# A-14732-40023-REPRODUCTION.net
KiCad netlist of a schematic drawn in EAGLE
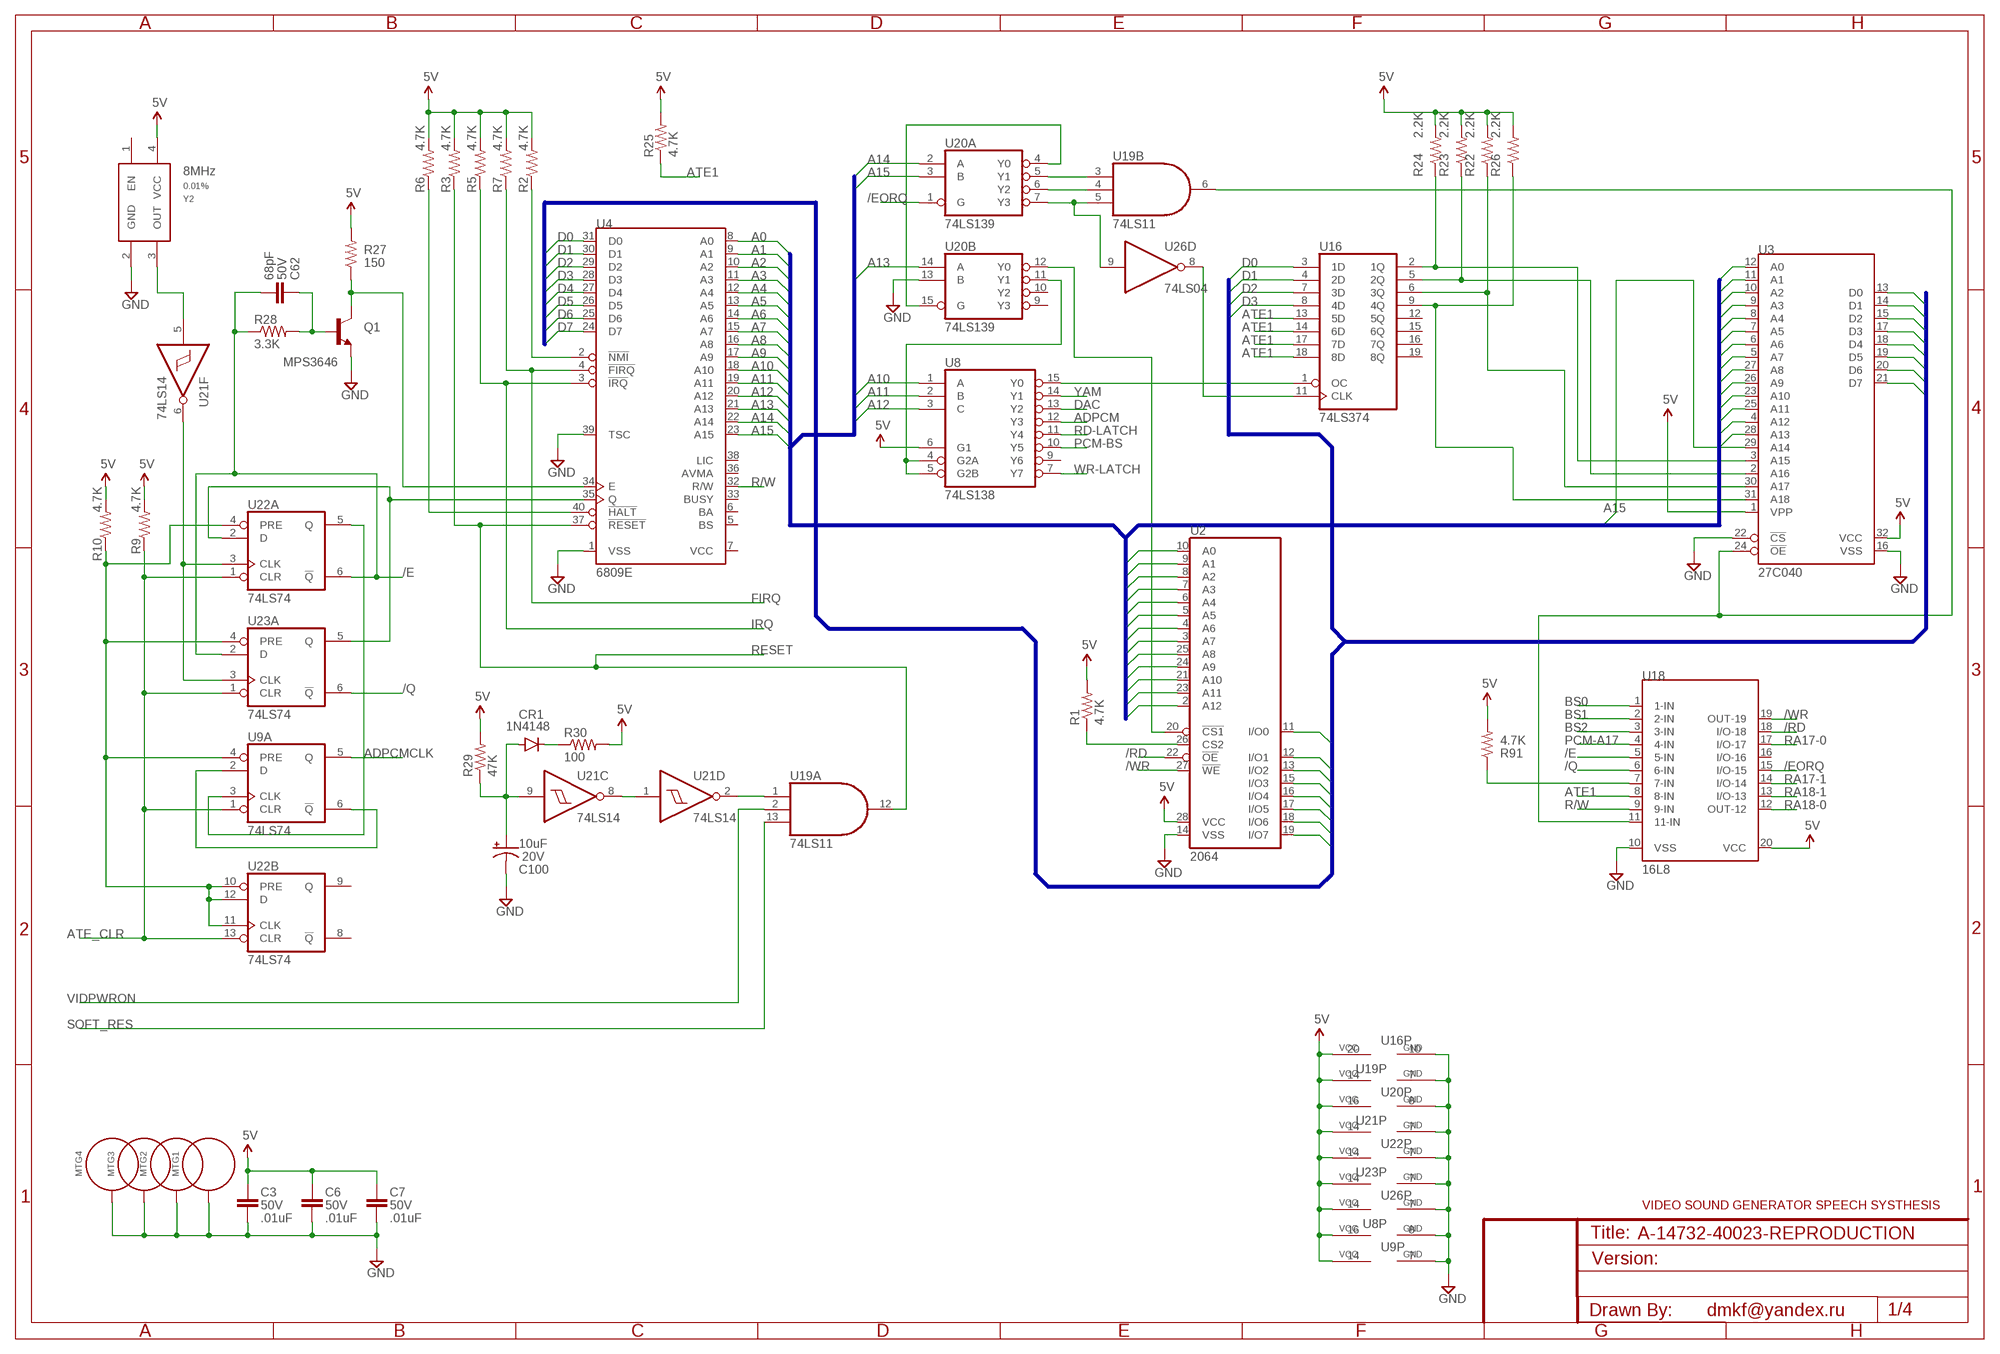
[diagram p0: schematic, sheet 1]
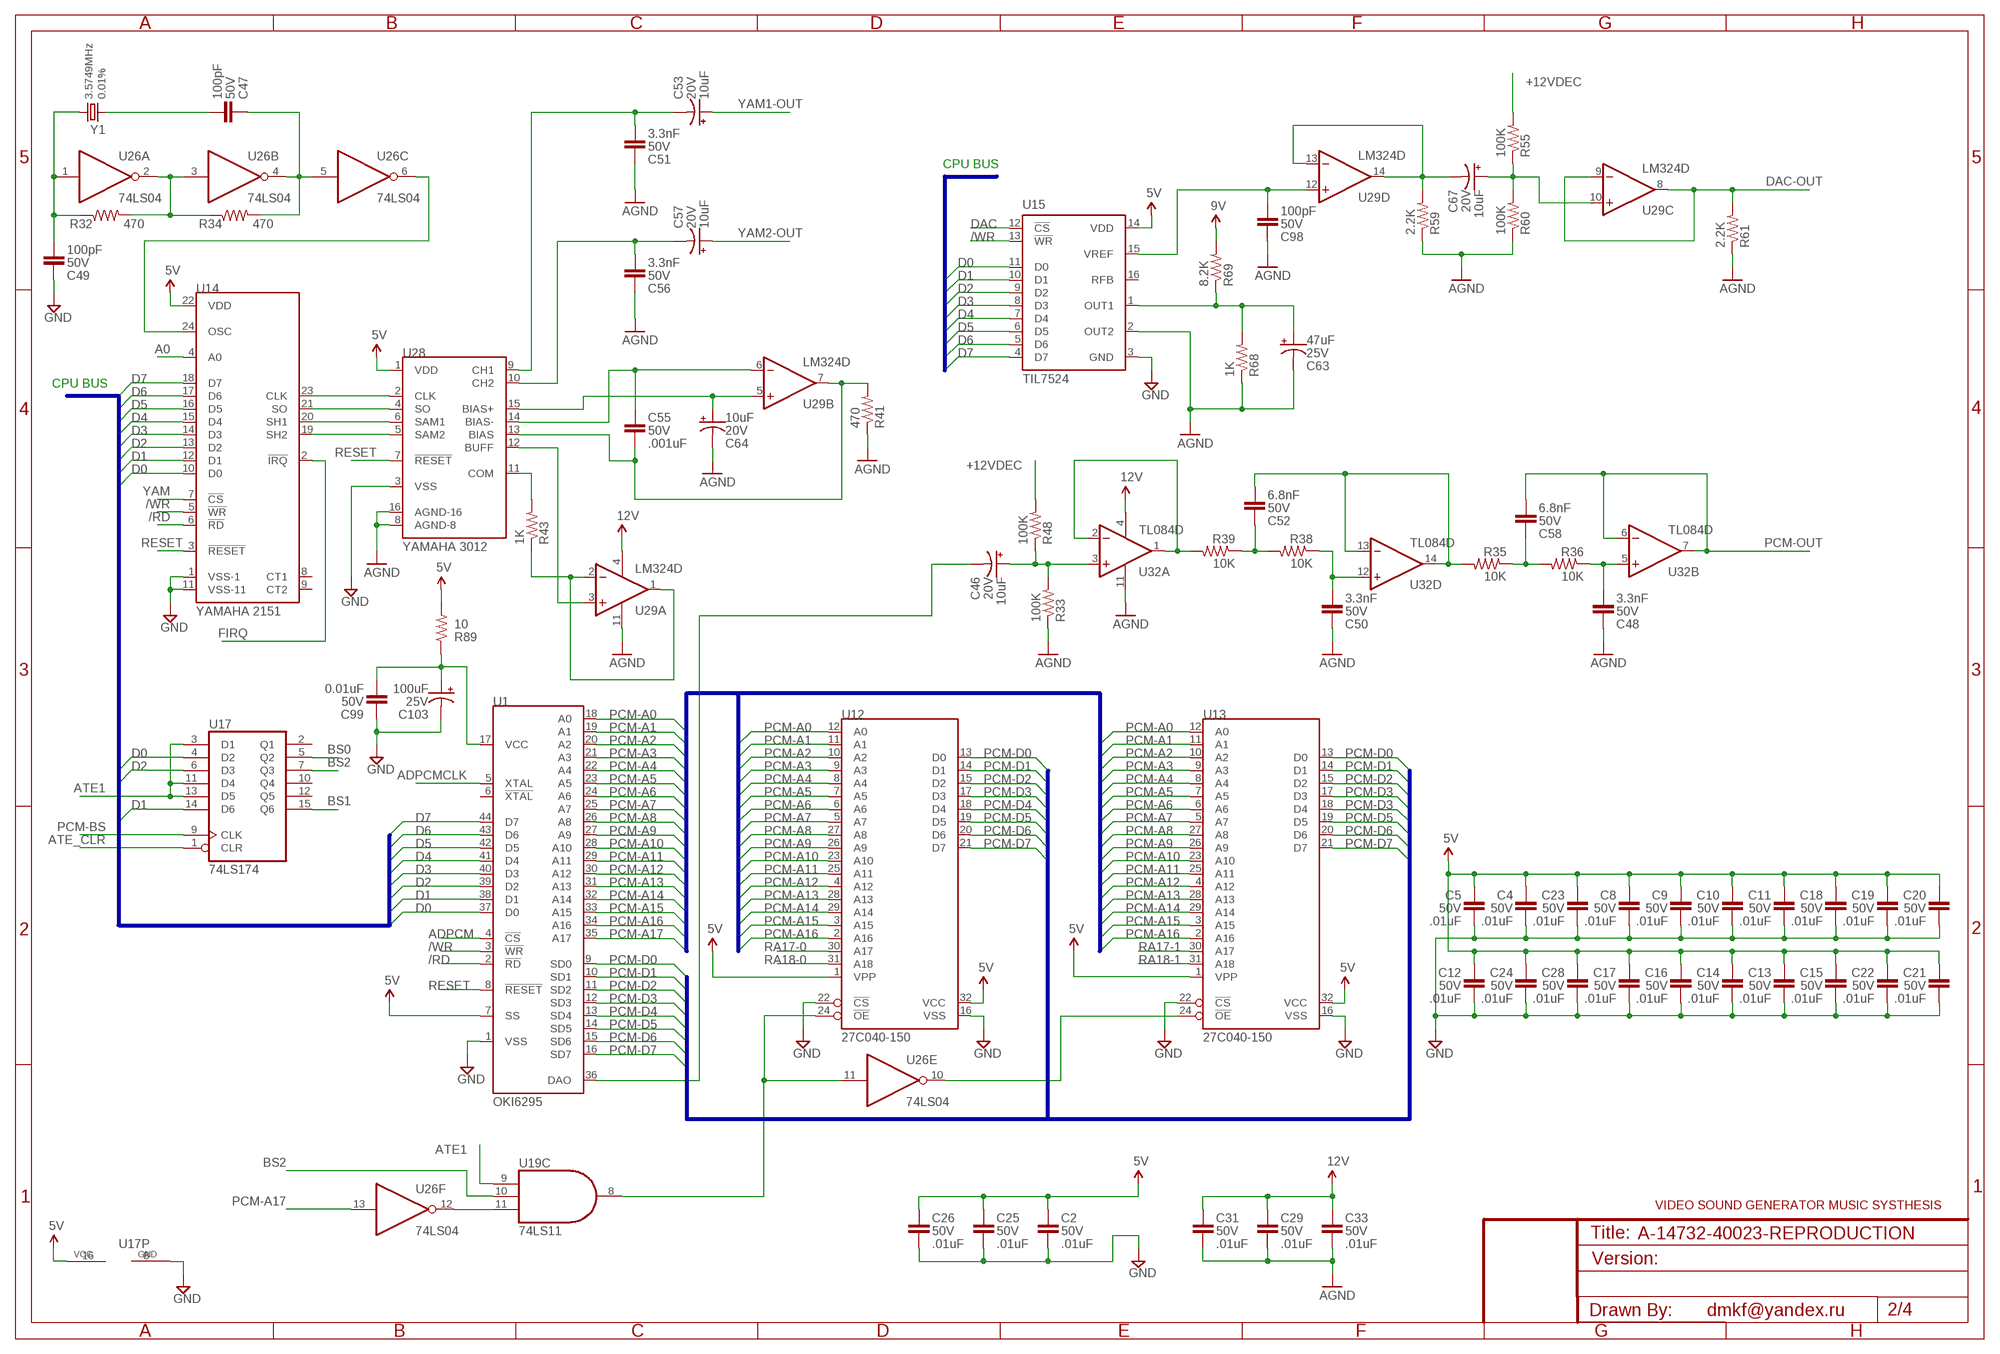
[diagram p1: schematic, sheet 2]
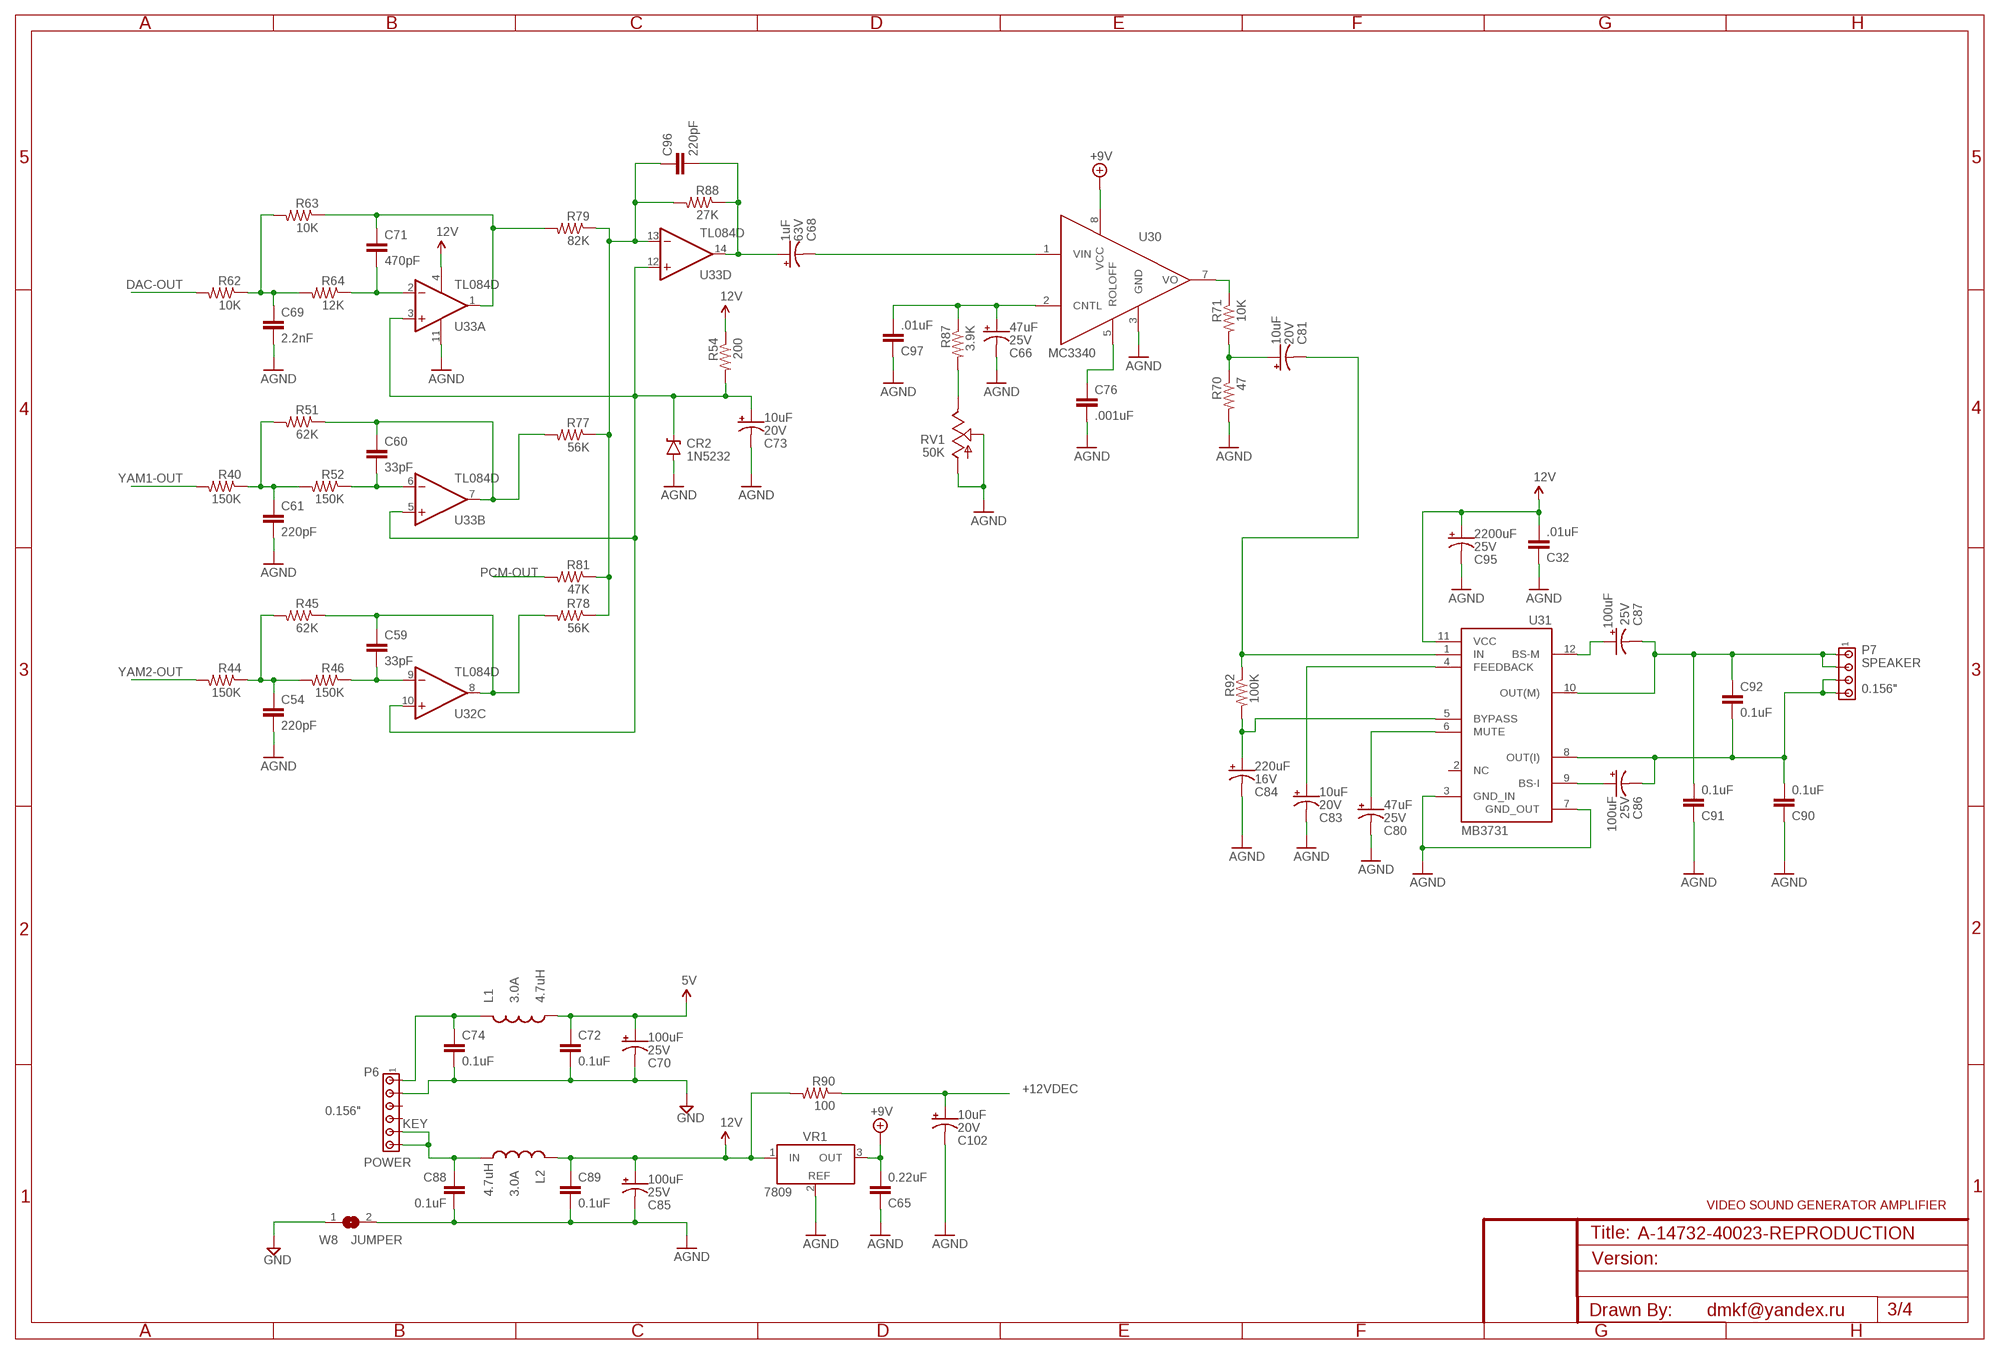
[diagram p2: schematic, sheet 3]
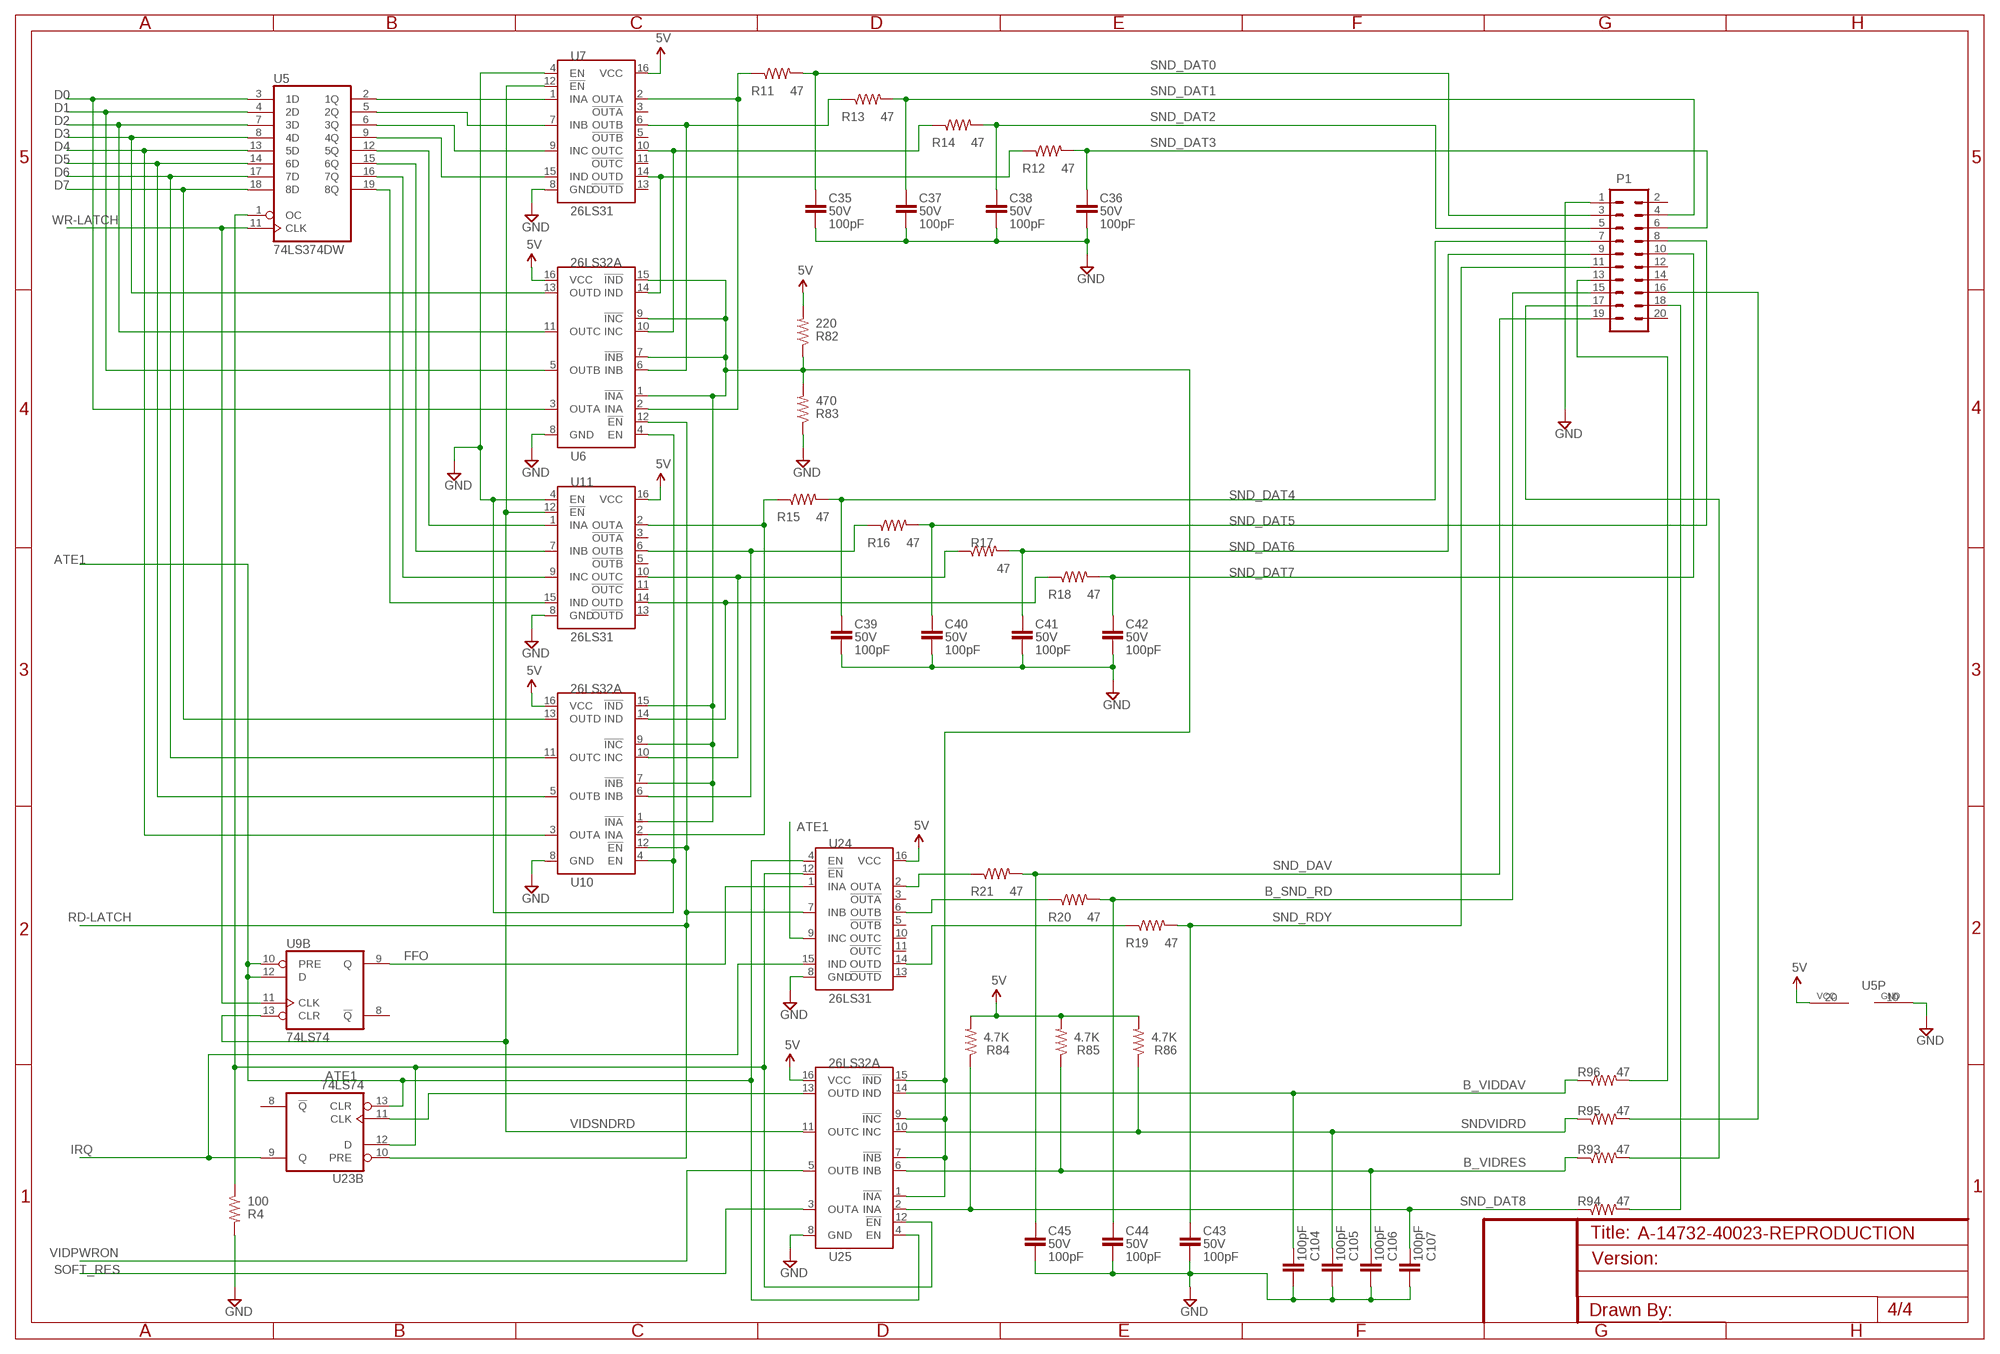
[diagram p3: schematic, sheet 4]

(export (version "E")
  (design (tool "Eeschema 10.0.6"))
  (components
    (comp (ref "C35")
      (value "100pF")
      (footprint "eagle-import:0805")
      (fields (field (name "VOLTAGE") "50V"))
      (libsource (lib "eagle-import") (part "CAP0805"))
    )
    (comp (ref "C36")
      (value "100pF")
      (footprint "eagle-import:0805")
      (fields (field (name "VOLTAGE") "50V"))
      (libsource (lib "eagle-import") (part "CAP0805"))
    )
    (comp (ref "C37")
      (value "100pF")
      (footprint "eagle-import:0805")
      (fields (field (name "VOLTAGE") "50V"))
      (libsource (lib "eagle-import") (part "CAP0805"))
    )
    (comp (ref "C38")
      (value "100pF")
      (footprint "eagle-import:0805")
      (fields (field (name "VOLTAGE") "50V"))
      (libsource (lib "eagle-import") (part "CAP0805"))
    )
    (comp (ref "C39")
      (value "100pF")
      (footprint "eagle-import:0805")
      (fields (field (name "VOLTAGE") "50V"))
      (libsource (lib "eagle-import") (part "CAP0805"))
    )
    (comp (ref "C40")
      (value "100pF")
      (footprint "eagle-import:0805")
      (fields (field (name "VOLTAGE") "50V"))
      (libsource (lib "eagle-import") (part "CAP0805"))
    )
    (comp (ref "C41")
      (value "100pF")
      (footprint "eagle-import:0805")
      (fields (field (name "VOLTAGE") "50V"))
      (libsource (lib "eagle-import") (part "CAP0805"))
    )
    (comp (ref "C42")
      (value "100pF")
      (footprint "eagle-import:0805")
      (fields (field (name "VOLTAGE") "50V"))
      (libsource (lib "eagle-import") (part "CAP0805"))
    )
    (comp (ref "C43")
      (value "100pF")
      (footprint "eagle-import:0805")
      (fields (field (name "VOLTAGE") "50V"))
      (libsource (lib "eagle-import") (part "CAP0805"))
    )
    (comp (ref "C44")
      (value "100pF")
      (footprint "eagle-import:0805")
      (fields (field (name "VOLTAGE") "50V"))
      (libsource (lib "eagle-import") (part "CAP0805"))
    )
    (comp (ref "C45")
      (value "100pF")
      (footprint "eagle-import:0805")
      (fields (field (name "VOLTAGE") "50V"))
      (libsource (lib "eagle-import") (part "CAP0805"))
    )
    (comp (ref "C104")
      (value "100pF")
      (footprint "eagle-import:0805")
      (fields (field (name "VOLTAGE") "50V"))
      (libsource (lib "eagle-import") (part "CAP0805"))
    )
    (comp (ref "C105")
      (value "100pF")
      (footprint "eagle-import:0805")
      (fields (field (name "VOLTAGE") "50V"))
      (libsource (lib "eagle-import") (part "CAP0805"))
    )
    (comp (ref "C106")
      (value "100pF")
      (footprint "eagle-import:0805")
      (fields (field (name "VOLTAGE") "50V"))
      (libsource (lib "eagle-import") (part "CAP0805"))
    )
    (comp (ref "C107")
      (value "100pF")
      (footprint "eagle-import:0805")
      (fields (field (name "VOLTAGE") "50V"))
      (libsource (lib "eagle-import") (part "CAP0805"))
    )
    (comp (ref "P1")
      (value "M10X2ROUND_NOSILK")
      (footprint "eagle-import:2X10_ROUND_NOSILK")
      (libsource (lib "eagle-import") (part "M10X2ROUND_NOSILK"))
    )
    (comp (ref "R4")
      (value "100")
      (footprint "eagle-import:0805")
      (libsource (lib "eagle-import") (part "RESISTOR0805-RES"))
    )
    (comp (ref "R11")
      (value "47")
      (footprint "eagle-import:0805")
      (libsource (lib "eagle-import") (part "RESISTOR0805-RES"))
    )
    (comp (ref "R12")
      (value "47")
      (footprint "eagle-import:0805")
      (libsource (lib "eagle-import") (part "RESISTOR0805-RES"))
    )
    (comp (ref "R13")
      (value "47")
      (footprint "eagle-import:0805")
      (libsource (lib "eagle-import") (part "RESISTOR0805-RES"))
    )
    (comp (ref "R14")
      (value "47")
      (footprint "eagle-import:0805")
      (libsource (lib "eagle-import") (part "RESISTOR0805-RES"))
    )
    (comp (ref "R15")
      (value "47")
      (footprint "eagle-import:R1206")
      (libsource (lib "eagle-import") (part "R-US_R1206"))
    )
    (comp (ref "R16")
      (value "47")
      (footprint "eagle-import:R1206")
      (libsource (lib "eagle-import") (part "R-US_R1206"))
    )
    (comp (ref "R17")
      (value "47")
      (footprint "eagle-import:R1206")
      (libsource (lib "eagle-import") (part "R-US_R1206"))
    )
    (comp (ref "R18")
      (value "47")
      (footprint "eagle-import:R1206")
      (libsource (lib "eagle-import") (part "R-US_R1206"))
    )
    (comp (ref "R19")
      (value "47")
      (footprint "eagle-import:0805")
      (libsource (lib "eagle-import") (part "RESISTOR0805-RES"))
    )
    (comp (ref "R20")
      (value "47")
      (footprint "eagle-import:0805")
      (libsource (lib "eagle-import") (part "RESISTOR0805-RES"))
    )
    (comp (ref "R21")
      (value "47")
      (footprint "eagle-import:0805")
      (libsource (lib "eagle-import") (part "RESISTOR0805-RES"))
    )
    (comp (ref "R82")
      (value "220")
      (footprint "eagle-import:R1206")
      (libsource (lib "eagle-import") (part "R-US_R1206"))
    )
    (comp (ref "R83")
      (value "470")
      (footprint "eagle-import:R1206")
      (libsource (lib "eagle-import") (part "R-US_R1206"))
    )
    (comp (ref "R84")
      (value "4.7K")
      (footprint "eagle-import:0805")
      (libsource (lib "eagle-import") (part "RESISTOR0805-RES"))
    )
    (comp (ref "R85")
      (value "4.7K")
      (footprint "eagle-import:0805")
      (libsource (lib "eagle-import") (part "RESISTOR0805-RES"))
    )
    (comp (ref "R86")
      (value "4.7K")
      (footprint "eagle-import:0805")
      (libsource (lib "eagle-import") (part "RESISTOR0805-RES"))
    )
    (comp (ref "R93")
      (value "47")
      (footprint "eagle-import:0805")
      (libsource (lib "eagle-import") (part "RESISTOR0805-RES"))
    )
    (comp (ref "R94")
      (value "47")
      (footprint "eagle-import:0805")
      (libsource (lib "eagle-import") (part "RESISTOR0805-RES"))
    )
    (comp (ref "R95")
      (value "47")
      (footprint "eagle-import:0805")
      (libsource (lib "eagle-import") (part "RESISTOR0805-RES"))
    )
    (comp (ref "R96")
      (value "47")
      (footprint "eagle-import:0805")
      (libsource (lib "eagle-import") (part "RESISTOR0805-RES"))
    )
    (comp (ref "U5")
      (value "74LS374DW")
      (footprint "eagle-import:SO20W")
      (libsource (lib "eagle-import") (part "74374DWLS"))
    )
    (comp (ref "U6")
      (value "26LS32A")
      (footprint "eagle-import:SO16")
      (libsource (lib "eagle-import") (part "26LS32A"))
    )
    (comp (ref "U7")
      (value "26LS31")
      (footprint "eagle-import:SO16")
      (libsource (lib "eagle-import") (part "26LS31"))
    )
    (comp (ref "U9")
      (value "74LS74")
      (footprint "eagle-import:SO14")
      (libsource (lib "eagle-import") (part "7474DLS"))
    )
    (comp (ref "U10")
      (value "26LS32A")
      (footprint "eagle-import:SO16")
      (libsource (lib "eagle-import") (part "26LS32A"))
    )
    (comp (ref "U11")
      (value "26LS31")
      (footprint "eagle-import:SO16")
      (libsource (lib "eagle-import") (part "26LS31"))
    )
    (comp (ref "U23")
      (value "74LS74")
      (footprint "eagle-import:SO14")
      (libsource (lib "eagle-import") (part "7474DLS"))
    )
    (comp (ref "U24")
      (value "26LS31")
      (footprint "eagle-import:SO16")
      (libsource (lib "eagle-import") (part "26LS31"))
    )
    (comp (ref "U25")
      (value "26LS32A")
      (footprint "eagle-import:SO16")
      (libsource (lib "eagle-import") (part "26LS32A"))
    )
    (comp (ref "C2")
      (value ".01uF")
      (footprint "eagle-import:0805")
      (fields (field (name "VOLTAGE") "50V"))
      (libsource (lib "eagle-import") (part "CAP0805"))
    )
    (comp (ref "C4")
      (value ".01uF")
      (footprint "eagle-import:0805")
      (fields (field (name "VOLTAGE") "50V"))
      (libsource (lib "eagle-import") (part "CAP0805"))
    )
    (comp (ref "C5")
      (value ".01uF")
      (footprint "eagle-import:0805")
      (fields (field (name "VOLTAGE") "50V"))
      (libsource (lib "eagle-import") (part "CAP0805"))
    )
    (comp (ref "C8")
      (value ".01uF")
      (footprint "eagle-import:0805")
      (fields (field (name "VOLTAGE") "50V"))
      (libsource (lib "eagle-import") (part "CAP0805"))
    )
    (comp (ref "C9")
      (value ".01uF")
      (footprint "eagle-import:0805")
      (fields (field (name "VOLTAGE") "50V"))
      (libsource (lib "eagle-import") (part "CAP0805"))
    )
    (comp (ref "C10")
      (value ".01uF")
      (footprint "eagle-import:0805")
      (fields (field (name "VOLTAGE") "50V"))
      (libsource (lib "eagle-import") (part "CAP0805"))
    )
    (comp (ref "C11")
      (value ".01uF")
      (footprint "eagle-import:0805")
      (fields (field (name "VOLTAGE") "50V"))
      (libsource (lib "eagle-import") (part "CAP0805"))
    )
    (comp (ref "C12")
      (value ".01uF")
      (footprint "eagle-import:0805")
      (fields (field (name "VOLTAGE") "50V"))
      (libsource (lib "eagle-import") (part "CAP0805"))
    )
    (comp (ref "C13")
      (value ".01uF")
      (footprint "eagle-import:0805")
      (fields (field (name "VOLTAGE") "50V"))
      (libsource (lib "eagle-import") (part "CAP0805"))
    )
    (comp (ref "C14")
      (value ".01uF")
      (footprint "eagle-import:0805")
      (fields (field (name "VOLTAGE") "50V"))
      (libsource (lib "eagle-import") (part "CAP0805"))
    )
    (comp (ref "C15")
      (value ".01uF")
      (footprint "eagle-import:0805")
      (fields (field (name "VOLTAGE") "50V"))
      (libsource (lib "eagle-import") (part "CAP0805"))
    )
    (comp (ref "C16")
      (value ".01uF")
      (footprint "eagle-import:0805")
      (fields (field (name "VOLTAGE") "50V"))
      (libsource (lib "eagle-import") (part "CAP0805"))
    )
    (comp (ref "C17")
      (value ".01uF")
      (footprint "eagle-import:0805")
      (fields (field (name "VOLTAGE") "50V"))
      (libsource (lib "eagle-import") (part "CAP0805"))
    )
    (comp (ref "C18")
      (value ".01uF")
      (footprint "eagle-import:0805")
      (fields (field (name "VOLTAGE") "50V"))
      (libsource (lib "eagle-import") (part "CAP0805"))
    )
    (comp (ref "C19")
      (value ".01uF")
      (footprint "eagle-import:0805")
      (fields (field (name "VOLTAGE") "50V"))
      (libsource (lib "eagle-import") (part "CAP0805"))
    )
    (comp (ref "C20")
      (value ".01uF")
      (footprint "eagle-import:0805")
      (fields (field (name "VOLTAGE") "50V"))
      (libsource (lib "eagle-import") (part "CAP0805"))
    )
    (comp (ref "C21")
      (value ".01uF")
      (footprint "eagle-import:0805")
      (fields (field (name "VOLTAGE") "50V"))
      (libsource (lib "eagle-import") (part "CAP0805"))
    )
    (comp (ref "C22")
      (value ".01uF")
      (footprint "eagle-import:0805")
      (fields (field (name "VOLTAGE") "50V"))
      (libsource (lib "eagle-import") (part "CAP0805"))
    )
    (comp (ref "C23")
      (value ".01uF")
      (footprint "eagle-import:0805")
      (fields (field (name "VOLTAGE") "50V"))
      (libsource (lib "eagle-import") (part "CAP0805"))
    )
    (comp (ref "C24")
      (value ".01uF")
      (footprint "eagle-import:0805")
      (fields (field (name "VOLTAGE") "50V"))
      (libsource (lib "eagle-import") (part "CAP0805"))
    )
    (comp (ref "C25")
      (value ".01uF")
      (footprint "eagle-import:0805")
      (fields (field (name "VOLTAGE") "50V"))
      (libsource (lib "eagle-import") (part "CAP0805"))
    )
    (comp (ref "C26")
      (value ".01uF")
      (footprint "eagle-import:0805")
      (fields (field (name "VOLTAGE") "50V"))
      (libsource (lib "eagle-import") (part "CAP0805"))
    )
    (comp (ref "C28")
      (value ".01uF")
      (footprint "eagle-import:0805")
      (fields (field (name "VOLTAGE") "50V"))
      (libsource (lib "eagle-import") (part "CAP0805"))
    )
    (comp (ref "C29")
      (value ".01uF")
      (footprint "eagle-import:0805")
      (fields (field (name "VOLTAGE") "50V"))
      (libsource (lib "eagle-import") (part "CAP0805"))
    )
    (comp (ref "C31")
      (value ".01uF")
      (footprint "eagle-import:0805")
      (fields (field (name "VOLTAGE") "50V"))
      (libsource (lib "eagle-import") (part "CAP0805"))
    )
    (comp (ref "C33")
      (value ".01uF")
      (footprint "eagle-import:0805")
      (fields (field (name "VOLTAGE") "50V"))
      (libsource (lib "eagle-import") (part "CAP0805"))
    )
    (comp (ref "C46")
      (value "10uF")
      (footprint "eagle-import:PANASONIC_C")
      (fields (field (name "VOLTAGE") "20V"))
      (libsource (lib "eagle-import") (part "CAP_POLC"))
    )
    (comp (ref "C47")
      (value "100pF")
      (footprint "eagle-import:0805")
      (fields (field (name "VOLTAGE") "50V"))
      (libsource (lib "eagle-import") (part "CAP0805"))
    )
    (comp (ref "C48")
      (value "3.3nF")
      (footprint "eagle-import:0805")
      (fields (field (name "VOLTAGE") "50V"))
      (libsource (lib "eagle-import") (part "CAP0805"))
    )
    (comp (ref "C49")
      (value "100pF")
      (footprint "eagle-import:0805")
      (fields (field (name "VOLTAGE") "50V"))
      (libsource (lib "eagle-import") (part "CAP0805"))
    )
    (comp (ref "C50")
      (value "3.3nF")
      (footprint "eagle-import:0805")
      (fields (field (name "VOLTAGE") "50V"))
      (libsource (lib "eagle-import") (part "CAP0805"))
    )
    (comp (ref "C51")
      (value "3.3nF")
      (footprint "eagle-import:0805")
      (fields (field (name "VOLTAGE") "50V"))
      (libsource (lib "eagle-import") (part "CAP0805"))
    )
    (comp (ref "C52")
      (value "6.8nF")
      (footprint "eagle-import:0805")
      (fields (field (name "VOLTAGE") "50V"))
      (libsource (lib "eagle-import") (part "CAP0805"))
    )
    (comp (ref "C53")
      (value "10uF")
      (footprint "eagle-import:PANASONIC_C")
      (fields (field (name "VOLTAGE") "20V"))
      (libsource (lib "eagle-import") (part "CAP_POLC"))
    )
    (comp (ref "C55")
      (value ".001uF")
      (footprint "eagle-import:0805")
      (fields (field (name "VOLTAGE") "50V"))
      (libsource (lib "eagle-import") (part "CAP0805"))
    )
    (comp (ref "C56")
      (value "3.3nF")
      (footprint "eagle-import:0805")
      (fields (field (name "VOLTAGE") "50V"))
      (libsource (lib "eagle-import") (part "CAP0805"))
    )
    (comp (ref "C57")
      (value "10uF")
      (footprint "eagle-import:PANASONIC_C")
      (fields (field (name "VOLTAGE") "20V"))
      (libsource (lib "eagle-import") (part "CAP_POLC"))
    )
    (comp (ref "C58")
      (value "6.8nF")
      (footprint "eagle-import:0805")
      (fields (field (name "VOLTAGE") "50V"))
      (libsource (lib "eagle-import") (part "CAP0805"))
    )
    (comp (ref "C63")
      (value "47uF")
      (footprint "eagle-import:PANASONIC_D")
      (fields (field (name "VOLTAGE") "25V"))
      (libsource (lib "eagle-import") (part "CAP_POLD"))
    )
    (comp (ref "C64")
      (value "10uF")
      (footprint "eagle-import:PANASONIC_C")
      (fields (field (name "VOLTAGE") "20V"))
      (libsource (lib "eagle-import") (part "CAP_POLC"))
    )
    (comp (ref "C67")
      (value "10uF")
      (footprint "eagle-import:PANASONIC_C")
      (fields (field (name "VOLTAGE") "20V"))
      (libsource (lib "eagle-import") (part "CAP_POLC"))
    )
    (comp (ref "C98")
      (value "100pF")
      (footprint "eagle-import:0805")
      (fields (field (name "VOLTAGE") "50V"))
      (libsource (lib "eagle-import") (part "CAP0805"))
    )
    (comp (ref "C99")
      (value "0.01uF")
      (footprint "eagle-import:0805")
      (fields (field (name "VOLTAGE") "50V"))
      (libsource (lib "eagle-import") (part "CAP0805"))
    )
    (comp (ref "C103")
      (value "100uF")
      (footprint "eagle-import:PANASONIC_D")
      (fields (field (name "VOLTAGE") "25V"))
      (libsource (lib "eagle-import") (part "CAP_POLD"))
    )
    (comp (ref "R32")
      (value "470")
      (footprint "eagle-import:0805")
      (libsource (lib "eagle-import") (part "RESISTOR0805-RES"))
    )
    (comp (ref "R33")
      (value "100K")
      (footprint "eagle-import:0805")
      (libsource (lib "eagle-import") (part "RESISTOR0805-RES"))
    )
    (comp (ref "R34")
      (value "470")
      (footprint "eagle-import:0805")
      (libsource (lib "eagle-import") (part "RESISTOR0805-RES"))
    )
    (comp (ref "R35")
      (value "10K")
      (footprint "eagle-import:0805")
      (libsource (lib "eagle-import") (part "RESISTOR0805-RES"))
    )
    (comp (ref "R36")
      (value "10K")
      (footprint "eagle-import:0805")
      (libsource (lib "eagle-import") (part "RESISTOR0805-RES"))
    )
    (comp (ref "R38")
      (value "10K")
      (footprint "eagle-import:0805")
      (libsource (lib "eagle-import") (part "RESISTOR0805-RES"))
    )
    (comp (ref "R39")
      (value "10K")
      (footprint "eagle-import:0805")
      (libsource (lib "eagle-import") (part "RESISTOR0805-RES"))
    )
    (comp (ref "R41")
      (value "470")
      (footprint "eagle-import:0805")
      (libsource (lib "eagle-import") (part "RESISTOR0805-RES"))
    )
    (comp (ref "R43")
      (value "1K")
      (footprint "eagle-import:0805")
      (libsource (lib "eagle-import") (part "RESISTOR0805-RES"))
    )
    (comp (ref "R48")
      (value "100K")
      (footprint "eagle-import:0805")
      (libsource (lib "eagle-import") (part "RESISTOR0805-RES"))
    )
    (comp (ref "R55")
      (value "100K")
      (footprint "eagle-import:0805")
      (libsource (lib "eagle-import") (part "RESISTOR0805-RES"))
    )
    (comp (ref "R59")
      (value "2.2K")
      (footprint "eagle-import:0805")
      (libsource (lib "eagle-import") (part "RESISTOR0805-RES"))
    )
    (comp (ref "R60")
      (value "100K")
      (footprint "eagle-import:0805")
      (libsource (lib "eagle-import") (part "RESISTOR0805-RES"))
    )
    (comp (ref "R61")
      (value "2.2K")
      (footprint "eagle-import:0805")
      (libsource (lib "eagle-import") (part "RESISTOR0805-RES"))
    )
    (comp (ref "R68")
      (value "1K")
      (footprint "eagle-import:0805")
      (libsource (lib "eagle-import") (part "RESISTOR0805-RES"))
    )
    (comp (ref "R69")
      (value "8.2K")
      (footprint "eagle-import:0805")
      (libsource (lib "eagle-import") (part "RESISTOR0805-RES"))
    )
    (comp (ref "R89")
      (value "10")
      (footprint "eagle-import:1206")
      (libsource (lib "eagle-import") (part "RESISTOR1206"))
    )
    (comp (ref "U1")
      (value "OKI6295")
      (footprint "eagle-import:QFP44")
      (libsource (lib "eagle-import") (part "OKI6295"))
    )
    (comp (ref "U12")
      (value "27C040-150")
      (footprint "eagle-import:PLCC32R")
      (libsource (lib "eagle-import") (part "27C040PLCC32"))
    )
    (comp (ref "U13")
      (value "27C040-150")
      (footprint "eagle-import:PLCC32R")
      (libsource (lib "eagle-import") (part "27C040PLCC32"))
    )
    (comp (ref "U14")
      (value "YAMAHA 2151")
      (footprint "eagle-import:DIP24")
      (libsource (lib "eagle-import") (part "YM2151"))
    )
    (comp (ref "U15")
      (value "TIL7524")
      (footprint "eagle-import:SOIC16N")
      (fields (field (name "MF") "ALTERA CORPORATION") (field (name "MPN") "AD7524JRZ"))
      (libsource (lib "eagle-import") (part "AD7524RJ"))
    )
    (comp (ref "U17")
      (value "74LS174")
      (footprint "eagle-import:SO16")
      (libsource (lib "eagle-import") (part "74174DLS"))
    )
    (comp (ref "U19")
      (value "74LS11")
      (footprint "eagle-import:SO14")
      (libsource (lib "eagle-import") (part "7411DLS"))
    )
    (comp (ref "U26")
      (value "74LS04")
      (footprint "eagle-import:SO14")
      (libsource (lib "eagle-import") (part "7404DLS"))
    )
    (comp (ref "U28")
      (value "YAMAHA 3012")
      (footprint "eagle-import:DIP16N")
      (libsource (lib "eagle-import") (part "YM3012"))
    )
    (comp (ref "U29")
      (value "LM324D")
      (footprint "eagle-import:SO14")
      (libsource (lib "eagle-import") (part "LM324D"))
    )
    (comp (ref "U32")
      (value "TL084D")
      (footprint "eagle-import:SO14")
      (libsource (lib "eagle-import") (part "TL084D"))
    )
    (comp (ref "Y1")
      (value "3.5749MHz")
      (footprint "eagle-import:HC49U-V")
      (fields (field (name "TOLERANCE") "0.01%"))
      (libsource (lib "eagle-import") (part "CRYSTALHC49U-V"))
    )
    (comp (ref "C32")
      (value ".01uF")
      (footprint "eagle-import:0805")
      (fields (field (name "VOLTAGE") "50V"))
      (libsource (lib "eagle-import") (part "CAP0805"))
    )
    (comp (ref "C54")
      (value "220pF")
      (footprint "eagle-import:0805")
      (fields (field (name "VOLTAGE") "50V"))
      (libsource (lib "eagle-import") (part "CAP0805"))
    )
    (comp (ref "C59")
      (value "33pF")
      (footprint "eagle-import:0805")
      (fields (field (name "VOLTAGE") "50V"))
      (libsource (lib "eagle-import") (part "CAP0805"))
    )
    (comp (ref "C60")
      (value "33pF")
      (footprint "eagle-import:0805")
      (fields (field (name "VOLTAGE") "50V"))
      (libsource (lib "eagle-import") (part "CAP0805"))
    )
    (comp (ref "C61")
      (value "220pF")
      (footprint "eagle-import:0805")
      (fields (field (name "VOLTAGE") "50V"))
      (libsource (lib "eagle-import") (part "CAP0805"))
    )
    (comp (ref "C65")
      (value "0.22uF")
      (footprint "eagle-import:0805")
      (fields (field (name "VOLTAGE") "50V"))
      (libsource (lib "eagle-import") (part "CAP0805"))
    )
    (comp (ref "C66")
      (value "47uF")
      (footprint "eagle-import:PANASONIC_D")
      (fields (field (name "VOLTAGE") "25V"))
      (libsource (lib "eagle-import") (part "CAP_POLD"))
    )
    (comp (ref "C68")
      (value "1uF")
      (footprint "eagle-import:PANASONIC_C")
      (fields (field (name "VOLTAGE") "63V"))
      (libsource (lib "eagle-import") (part "CAP_POLC"))
    )
    (comp (ref "C69")
      (value "2.2nF")
      (footprint "eagle-import:0805")
      (fields (field (name "VOLTAGE") "50V"))
      (libsource (lib "eagle-import") (part "CAP0805"))
    )
    (comp (ref "C70")
      (value "100uF")
      (footprint "eagle-import:PANASONIC_D")
      (fields (field (name "VOLTAGE") "25V"))
      (libsource (lib "eagle-import") (part "CAP_POLD"))
    )
    (comp (ref "C71")
      (value "470pF")
      (footprint "eagle-import:0805")
      (fields (field (name "VOLTAGE") "50V"))
      (libsource (lib "eagle-import") (part "CAP0805"))
    )
    (comp (ref "C72")
      (value "0.1uF")
      (footprint "eagle-import:0805")
      (fields (field (name "VOLTAGE") "50V"))
      (libsource (lib "eagle-import") (part "CAP0805"))
    )
    (comp (ref "C73")
      (value "10uF")
      (footprint "eagle-import:PANASONIC_C")
      (fields (field (name "VOLTAGE") "20V"))
      (libsource (lib "eagle-import") (part "CAP_POLC"))
    )
    (comp (ref "C74")
      (value "0.1uF")
      (footprint "eagle-import:0805")
      (fields (field (name "VOLTAGE") "50V"))
      (libsource (lib "eagle-import") (part "CAP0805"))
    )
    (comp (ref "C76")
      (value ".001uF")
      (footprint "eagle-import:0805")
      (fields (field (name "VOLTAGE") "50V"))
      (libsource (lib "eagle-import") (part "CAP0805"))
    )
    (comp (ref "C80")
      (value "47uF")
      (footprint "eagle-import:PANASONIC_D")
      (fields (field (name "VOLTAGE") "25V"))
      (libsource (lib "eagle-import") (part "CAP_POLD"))
    )
    (comp (ref "C81")
      (value "10uF")
      (footprint "eagle-import:PANASONIC_C")
      (fields (field (name "VOLTAGE") "20V"))
      (libsource (lib "eagle-import") (part "CAP_POLC"))
    )
    (comp (ref "C83")
      (value "10uF")
      (footprint "eagle-import:PANASONIC_C")
      (fields (field (name "VOLTAGE") "20V"))
      (libsource (lib "eagle-import") (part "CAP_POLC"))
    )
    (comp (ref "C84")
      (value "220uF")
      (footprint "eagle-import:PANASONIC_E")
      (fields (field (name "VOLTAGE") "16V"))
      (libsource (lib "eagle-import") (part "CAP_POLE"))
    )
    (comp (ref "C85")
      (value "100uF")
      (footprint "eagle-import:PANASONIC_D")
      (fields (field (name "VOLTAGE") "25V"))
      (libsource (lib "eagle-import") (part "CAP_POLD"))
    )
    (comp (ref "C86")
      (value "100uF")
      (footprint "eagle-import:PANASONIC_D")
      (fields (field (name "VOLTAGE") "25V"))
      (libsource (lib "eagle-import") (part "CAP_POLD"))
    )
    (comp (ref "C87")
      (value "100uF")
      (footprint "eagle-import:PANASONIC_D")
      (fields (field (name "VOLTAGE") "25V"))
      (libsource (lib "eagle-import") (part "CAP_POLD"))
    )
    (comp (ref "C88")
      (value "0.1uF")
      (footprint "eagle-import:0805")
      (fields (field (name "VOLTAGE") "50V"))
      (libsource (lib "eagle-import") (part "CAP0805"))
    )
    (comp (ref "C89")
      (value "0.1uF")
      (footprint "eagle-import:0805")
      (fields (field (name "VOLTAGE") "50V"))
      (libsource (lib "eagle-import") (part "CAP0805"))
    )
    (comp (ref "C90")
      (value "0.1uF")
      (footprint "eagle-import:0805")
      (fields (field (name "VOLTAGE") "50V"))
      (libsource (lib "eagle-import") (part "CAP0805"))
    )
    (comp (ref "C91")
      (value "0.1uF")
      (footprint "eagle-import:0805")
      (fields (field (name "VOLTAGE") "50V"))
      (libsource (lib "eagle-import") (part "CAP0805"))
    )
    (comp (ref "C92")
      (value "0.1uF")
      (footprint "eagle-import:0805")
      (fields (field (name "VOLTAGE") "50V"))
      (libsource (lib "eagle-import") (part "CAP0805"))
    )
    (comp (ref "C95")
      (value "2200uF")
      (footprint "eagle-import:CPOL-RADIAL-1000UF-25V")
      (fields (field (name "VOLTAGE") "25V"))
      (libsource (lib "eagle-import") (part "CAP_POLPTH4"))
    )
    (comp (ref "C96")
      (value "220pF")
      (footprint "eagle-import:0805")
      (fields (field (name "VOLTAGE") "50V"))
      (libsource (lib "eagle-import") (part "CAP0805"))
    )
    (comp (ref "C97")
      (value ".01uF")
      (footprint "eagle-import:0805")
      (fields (field (name "VOLTAGE") "50V"))
      (libsource (lib "eagle-import") (part "CAP0805"))
    )
    (comp (ref "C102")
      (value "10uF")
      (footprint "eagle-import:PANASONIC_C")
      (fields (field (name "VOLTAGE") "20V"))
      (libsource (lib "eagle-import") (part "CAP_POLC"))
    )
    (comp (ref "CR2")
      (value "1N5232")
      (footprint "eagle-import:SOT23")
      (libsource (lib "eagle-import") (part "1N5232"))
    )
    (comp (ref "L1")
      (value "4.7uH")
      (footprint "eagle-import:NPI75C")
      (fields (field (name "CUR") "3.0A"))
      (libsource (lib "eagle-import") (part "INDUCTORNPI75"))
    )
    (comp (ref "L2")
      (value "4.7uH")
      (footprint "eagle-import:NPI75C")
      (fields (field (name "CURRENT") "3.0A"))
      (libsource (lib "eagle-import") (part "INDUCTORNPI75"))
    )
    (comp (ref "P6")
      (value "POWER")
      (footprint "eagle-import:1X6MTA")
      (fields (field (name "PITCH") "0.156\""))
      (libsource (lib "eagle-import") (part "MTA06-156"))
    )
    (comp (ref "P7")
      (value "SPEAKER")
      (footprint "eagle-import:1X4MTA")
      (fields (field (name "PITCH") "0.156\""))
      (libsource (lib "eagle-import") (part "MTA04-156"))
    )
    (comp (ref "R40")
      (value "150K")
      (footprint "eagle-import:0805")
      (libsource (lib "eagle-import") (part "RESISTOR0805-RES"))
    )
    (comp (ref "R44")
      (value "150K")
      (footprint "eagle-import:0805")
      (libsource (lib "eagle-import") (part "RESISTOR0805-RES"))
    )
    (comp (ref "R45")
      (value "62K")
      (footprint "eagle-import:0805")
      (libsource (lib "eagle-import") (part "RESISTOR0805-RES"))
    )
    (comp (ref "R46")
      (value "150K")
      (footprint "eagle-import:0805")
      (libsource (lib "eagle-import") (part "RESISTOR0805-RES"))
    )
    (comp (ref "R51")
      (value "62K")
      (footprint "eagle-import:0805")
      (libsource (lib "eagle-import") (part "RESISTOR0805-RES"))
    )
    (comp (ref "R52")
      (value "150K")
      (footprint "eagle-import:0805")
      (libsource (lib "eagle-import") (part "RESISTOR0805-RES"))
    )
    (comp (ref "R54")
      (value "200")
      (footprint "eagle-import:R1206")
      (libsource (lib "eagle-import") (part "R-US_R1206"))
    )
    (comp (ref "R62")
      (value "10K")
      (footprint "eagle-import:0805")
      (libsource (lib "eagle-import") (part "RESISTOR0805-RES"))
    )
    (comp (ref "R63")
      (value "10K")
      (footprint "eagle-import:0805")
      (libsource (lib "eagle-import") (part "RESISTOR0805-RES"))
    )
    (comp (ref "R64")
      (value "12K")
      (footprint "eagle-import:0805")
      (libsource (lib "eagle-import") (part "RESISTOR0805-RES"))
    )
    (comp (ref "R70")
      (value "47")
      (footprint "eagle-import:R1206")
      (libsource (lib "eagle-import") (part "R-US_R1206"))
    )
    (comp (ref "R71")
      (value "10K")
      (footprint "eagle-import:0805")
      (libsource (lib "eagle-import") (part "RESISTOR0805-RES"))
    )
    (comp (ref "R77")
      (value "56K")
      (footprint "eagle-import:0805")
      (libsource (lib "eagle-import") (part "RESISTOR0805-RES"))
    )
    (comp (ref "R78")
      (value "56K")
      (footprint "eagle-import:0805")
      (libsource (lib "eagle-import") (part "RESISTOR0805-RES"))
    )
    (comp (ref "R79")
      (value "82K")
      (footprint "eagle-import:0805")
      (libsource (lib "eagle-import") (part "RESISTOR0805-RES"))
    )
    (comp (ref "R81")
      (value "47K")
      (footprint "eagle-import:0805")
      (libsource (lib "eagle-import") (part "RESISTOR0805-RES"))
    )
    (comp (ref "R87")
      (value "3.9K")
      (footprint "eagle-import:0805")
      (libsource (lib "eagle-import") (part "RESISTOR0805-RES"))
    )
    (comp (ref "R88")
      (value "27K")
      (footprint "eagle-import:0805")
      (libsource (lib "eagle-import") (part "RESISTOR0805-RES"))
    )
    (comp (ref "R90")
      (value "100")
      (footprint "eagle-import:R1206")
      (libsource (lib "eagle-import") (part "R-US_R1206"))
    )
    (comp (ref "R92")
      (value "100K")
      (footprint "eagle-import:0805")
      (libsource (lib "eagle-import") (part "RESISTOR0805-RES"))
    )
    (comp (ref "RV1")
      (value "50K")
      (footprint "eagle-import:POT_ALPHA_RV16AF-20")
      (libsource (lib "eagle-import") (part "POT-RV16AF-20"))
    )
    (comp (ref "U30")
      (value "MC3340")
      (footprint "eagle-import:MC3340")
      (libsource (lib "eagle-import") (part "MC3340"))
    )
    (comp (ref "U31")
      (value "MB3731")
      (footprint "eagle-import:SIP12")
      (libsource (lib "eagle-import") (part "MB3731"))
    )
    (comp (ref "U33")
      (value "TL084D")
      (footprint "eagle-import:SO14")
      (libsource (lib "eagle-import") (part "TL084D"))
    )
    (comp (ref "VR1")
      (value "7809")
      (footprint "eagle-import:7809-TO220V")
      (fields (field (name "PARTNUMBER") "5460-12743-00"))
      (libsource (lib "eagle-import") (part "7809TO220"))
    )
    (comp (ref "W8")
      (value "JUMPER")
      (footprint "eagle-import:SJ")
      (libsource (lib "eagle-import") (part "SJ"))
    )
    (comp (ref "C3")
      (value ".01uF")
      (footprint "eagle-import:0805")
      (fields (field (name "VOLTAGE") "50V"))
      (libsource (lib "eagle-import") (part "CAP0805"))
    )
    (comp (ref "C6")
      (value ".01uF")
      (footprint "eagle-import:0805")
      (fields (field (name "VOLTAGE") "50V"))
      (libsource (lib "eagle-import") (part "CAP0805"))
    )
    (comp (ref "C7")
      (value ".01uF")
      (footprint "eagle-import:0805")
      (fields (field (name "VOLTAGE") "50V"))
      (libsource (lib "eagle-import") (part "CAP0805"))
    )
    (comp (ref "C62")
      (value "68pF")
      (footprint "eagle-import:0805")
      (libsource (lib "eagle-import") (part "CAP0805"))
    )
    (comp (ref "C100")
      (value "10uF")
      (footprint "eagle-import:PANASONIC_C")
      (fields (field (name "VOLTAGE") "20V"))
      (libsource (lib "eagle-import") (part "CAP_POLC"))
    )
    (comp (ref "CR1")
      (value "1N4148")
      (footprint "eagle-import:SMA-DIODE")
      (libsource (lib "eagle-import") (part "DIODESMA"))
    )
    (comp (ref "MTG1")
      (value "MTGHOLE")
      (footprint "eagle-import:STANDOFF-ELECTRICAL")
      (libsource (lib "eagle-import") (part "STANDOFF_ELECTRICAL"))
    )
    (comp (ref "MTG2")
      (value "MTGHOLE")
      (footprint "eagle-import:STANDOFF-ELECTRICAL")
      (libsource (lib "eagle-import") (part "STANDOFF_ELECTRICAL"))
    )
    (comp (ref "MTG3")
      (value "MTGHOLE")
      (footprint "eagle-import:STANDOFF-ELECTRICAL")
      (libsource (lib "eagle-import") (part "STANDOFF_ELECTRICAL"))
    )
    (comp (ref "MTG4")
      (value "MTGHOLE")
      (footprint "eagle-import:STANDOFF-ELECTRICAL")
      (libsource (lib "eagle-import") (part "STANDOFF_ELECTRICAL"))
    )
    (comp (ref "Q1")
      (value "MPS3646")
      (footprint "eagle-import:SOT23-3")
      (libsource (lib "eagle-import") (part "TRANSISTOR_NPNMMBT2222A"))
    )
    (comp (ref "R1")
      (value "4.7K")
      (footprint "eagle-import:0805")
      (libsource (lib "eagle-import") (part "RESISTOR0805-RES"))
    )
    (comp (ref "R2")
      (value "4.7K")
      (footprint "eagle-import:0805")
      (libsource (lib "eagle-import") (part "RESISTOR0805-RES"))
    )
    (comp (ref "R3")
      (value "4.7K")
      (footprint "eagle-import:0805")
      (libsource (lib "eagle-import") (part "RESISTOR0805-RES"))
    )
    (comp (ref "R5")
      (value "4.7K")
      (footprint "eagle-import:0805")
      (libsource (lib "eagle-import") (part "RESISTOR0805-RES"))
    )
    (comp (ref "R6")
      (value "4.7K")
      (footprint "eagle-import:0805")
      (libsource (lib "eagle-import") (part "RESISTOR0805-RES"))
    )
    (comp (ref "R7")
      (value "4.7K")
      (footprint "eagle-import:0805")
      (libsource (lib "eagle-import") (part "RESISTOR0805-RES"))
    )
    (comp (ref "R9")
      (value "4.7K")
      (footprint "eagle-import:0805")
      (libsource (lib "eagle-import") (part "RESISTOR0805-RES"))
    )
    (comp (ref "R10")
      (value "4.7K")
      (footprint "eagle-import:0805")
      (libsource (lib "eagle-import") (part "RESISTOR0805-RES"))
    )
    (comp (ref "R22")
      (value "2.2K")
      (footprint "eagle-import:0805")
      (libsource (lib "eagle-import") (part "RESISTOR0805-RES"))
    )
    (comp (ref "R23")
      (value "2.2K")
      (footprint "eagle-import:0805")
      (libsource (lib "eagle-import") (part "RESISTOR0805-RES"))
    )
    (comp (ref "R24")
      (value "2.2K")
      (footprint "eagle-import:0805")
      (libsource (lib "eagle-import") (part "RESISTOR0805-RES"))
    )
    (comp (ref "R25")
      (value "4.7K")
      (footprint "eagle-import:0805")
      (libsource (lib "eagle-import") (part "RESISTOR0805-RES"))
    )
    (comp (ref "R26")
      (value "2.2K")
      (footprint "eagle-import:0805")
      (libsource (lib "eagle-import") (part "RESISTOR0805-RES"))
    )
    (comp (ref "R27")
      (value "150")
      (footprint "eagle-import:1206")
      (libsource (lib "eagle-import") (part "RESISTOR1206"))
    )
    (comp (ref "R28")
      (value "3.3K")
      (footprint "eagle-import:0805")
      (libsource (lib "eagle-import") (part "RESISTOR0805-RES"))
    )
    (comp (ref "R29")
      (value "47K")
      (footprint "eagle-import:0805")
      (libsource (lib "eagle-import") (part "RESISTOR0805-RES"))
    )
    (comp (ref "R30")
      (value "100")
      (footprint "eagle-import:1206")
      (libsource (lib "eagle-import") (part "RESISTOR1206"))
    )
    (comp (ref "R91")
      (value "4.7K")
      (footprint "eagle-import:0805")
      (libsource (lib "eagle-import") (part "RESISTOR0805-RES"))
    )
    (comp (ref "U2")
      (value "2064")
      (footprint "eagle-import:SOP28")
      (libsource (lib "eagle-import") (part "MS6264LSOP28"))
    )
    (comp (ref "U3")
      (value "27C040")
      (footprint "eagle-import:PLCC32R")
      (libsource (lib "eagle-import") (part "27C040PLCC32"))
    )
    (comp (ref "U4")
      (value "6809E")
      (footprint "eagle-import:DIP40")
      (libsource (lib "eagle-import") (part "6809E"))
    )
    (comp (ref "U8")
      (value "74LS138")
      (footprint "eagle-import:SO16")
      (libsource (lib "eagle-import") (part "74138DLS"))
    )
    (comp (ref "U16")
      (value "74LS374")
      (footprint "eagle-import:SO20W")
      (libsource (lib "eagle-import") (part "74374DWLS"))
    )
    (comp (ref "U18")
      (value "16L8")
      (footprint "eagle-import:DIP20N")
      (libsource (lib "eagle-import") (part "PAL16L8"))
    )
    (comp (ref "U20")
      (value "74LS139")
      (footprint "eagle-import:SO16")
      (libsource (lib "eagle-import") (part "74139DLS"))
    )
    (comp (ref "U21")
      (value "74LS14")
      (footprint "eagle-import:SO14")
      (libsource (lib "eagle-import") (part "7414DLS"))
    )
    (comp (ref "U22")
      (value "74LS74")
      (footprint "eagle-import:SO14")
      (libsource (lib "eagle-import") (part "7474DLS"))
    )
    (comp (ref "Y2")
      (value "8MHz")
      (footprint "eagle-import:CRYSTAL-OSC-SMD-5X3")
      (fields (field (name "TOLERANCE") "0.01%"))
      (libsource (lib "eagle-import") (part "OSCILLATOR5X3-PIN1-INDICATED"))
    )
  )
  (nets
    (net (code "1") (name "+9V") (class "Default")
      (node (ref "C65") (pin "2") (pinfunction "2_2") (pintype "passive"))
      (node (ref "U30") (pin "8") (pinfunction "VCC_8") (pintype "power_in"))
      (node (ref "VR1") (pin "3") (pinfunction "OUT_3") (pintype "passive"))
    )
    (net (code "2") (name "+12VDEC") (class "Default")
      (node (ref "C102") (pin "+") (pinfunction "+_+") (pintype "passive"))
      (node (ref "R48") (pin "2") (pinfunction "2_2") (pintype "passive"))
      (node (ref "R55") (pin "2") (pinfunction "2_2") (pintype "passive"))
      (node (ref "R90") (pin "1") (pinfunction "1_1") (pintype "passive"))
    )
    (net (code "3") (name "5V") (class "Default")
      (node (ref "C10") (pin "1") (pinfunction "1_1") (pintype "passive"))
      (node (ref "C11") (pin "1") (pinfunction "1_1") (pintype "passive"))
      (node (ref "C12") (pin "1") (pinfunction "1_1") (pintype "passive"))
      (node (ref "C13") (pin "1") (pinfunction "1_1") (pintype "passive"))
      (node (ref "C14") (pin "1") (pinfunction "1_1") (pintype "passive"))
      (node (ref "C15") (pin "1") (pinfunction "1_1") (pintype "passive"))
      (node (ref "C16") (pin "1") (pinfunction "1_1") (pintype "passive"))
      (node (ref "C17") (pin "1") (pinfunction "1_1") (pintype "passive"))
      (node (ref "C18") (pin "1") (pinfunction "1_1") (pintype "passive"))
      (node (ref "C19") (pin "1") (pinfunction "1_1") (pintype "passive"))
      (node (ref "C2") (pin "1") (pinfunction "1_1") (pintype "passive"))
      (node (ref "C20") (pin "1") (pinfunction "1_1") (pintype "passive"))
      (node (ref "C21") (pin "1") (pinfunction "1_1") (pintype "passive"))
      (node (ref "C22") (pin "1") (pinfunction "1_1") (pintype "passive"))
      (node (ref "C23") (pin "1") (pinfunction "1_1") (pintype "passive"))
      (node (ref "C24") (pin "1") (pinfunction "1_1") (pintype "passive"))
      (node (ref "C25") (pin "1") (pinfunction "1_1") (pintype "passive"))
      (node (ref "C26") (pin "1") (pinfunction "1_1") (pintype "passive"))
      (node (ref "C28") (pin "1") (pinfunction "1_1") (pintype "passive"))
      (node (ref "C3") (pin "1") (pinfunction "1_1") (pintype "passive"))
      (node (ref "C4") (pin "1") (pinfunction "1_1") (pintype "passive"))
      (node (ref "C5") (pin "1") (pinfunction "1_1") (pintype "passive"))
      (node (ref "C6") (pin "1") (pinfunction "1_1") (pintype "passive"))
      (node (ref "C7") (pin "1") (pinfunction "1_1") (pintype "passive"))
      (node (ref "C70") (pin "+") (pinfunction "+_+") (pintype "passive"))
      (node (ref "C72") (pin "1") (pinfunction "1_1") (pintype "passive"))
      (node (ref "C8") (pin "1") (pinfunction "1_1") (pintype "passive"))
      (node (ref "C9") (pin "1") (pinfunction "1_1") (pintype "passive"))
      (node (ref "L1") (pin "1") (pinfunction "1_1") (pintype "passive"))
      (node (ref "R1") (pin "2") (pinfunction "2_2") (pintype "passive"))
      (node (ref "R10") (pin "2") (pinfunction "2_2") (pintype "passive"))
      (node (ref "R2") (pin "2") (pinfunction "2_2") (pintype "passive"))
      (node (ref "R22") (pin "2") (pinfunction "2_2") (pintype "passive"))
      (node (ref "R23") (pin "2") (pinfunction "2_2") (pintype "passive"))
      (node (ref "R24") (pin "2") (pinfunction "2_2") (pintype "passive"))
      (node (ref "R25") (pin "2") (pinfunction "2_2") (pintype "passive"))
      (node (ref "R26") (pin "2") (pinfunction "2_2") (pintype "passive"))
      (node (ref "R27") (pin "2") (pinfunction "2_2") (pintype "passive"))
      (node (ref "R29") (pin "2") (pinfunction "2_2") (pintype "passive"))
      (node (ref "R3") (pin "2") (pinfunction "2_2") (pintype "passive"))
      (node (ref "R30") (pin "2") (pinfunction "2_2") (pintype "passive"))
      (node (ref "R5") (pin "2") (pinfunction "2_2") (pintype "passive"))
      (node (ref "R6") (pin "2") (pinfunction "2_2") (pintype "passive"))
      (node (ref "R69") (pin "2") (pinfunction "2_2") (pintype "passive"))
      (node (ref "R7") (pin "2") (pinfunction "2_2") (pintype "passive"))
      (node (ref "R82") (pin "2") (pinfunction "2_2") (pintype "passive"))
      (node (ref "R84") (pin "2") (pinfunction "2_2") (pintype "passive"))
      (node (ref "R85") (pin "2") (pinfunction "2_2") (pintype "passive"))
      (node (ref "R86") (pin "2") (pinfunction "2_2") (pintype "passive"))
      (node (ref "R89") (pin "2") (pinfunction "2_2") (pintype "passive"))
      (node (ref "R9") (pin "2") (pinfunction "2_2") (pintype "passive"))
      (node (ref "R91") (pin "2") (pinfunction "2_2") (pintype "passive"))
      (node (ref "U1") (pin "7") (pinfunction "SS_7") (pintype "passive"))
      (node (ref "U10") (pin "16") (pinfunction "VCC_16") (pintype "power_in"))
      (node (ref "U11") (pin "16") (pinfunction "VCC_16") (pintype "power_in"))
      (node (ref "U12") (pin "1") (pinfunction "VPP_1") (pintype "passive"))
      (node (ref "U12") (pin "32") (pinfunction "VCC_32") (pintype "passive"))
      (node (ref "U13") (pin "1") (pinfunction "VPP_1") (pintype "passive"))
      (node (ref "U13") (pin "32") (pinfunction "VCC_32") (pintype "passive"))
      (node (ref "U14") (pin "22") (pinfunction "VDD_22") (pintype "passive"))
      (node (ref "U15") (pin "14") (pinfunction "VDD_14") (pintype "power_in"))
      (node (ref "U16") (pin "20") (pinfunction "VCC_20") (pintype "power_in"))
      (node (ref "U17") (pin "16") (pinfunction "VCC_16") (pintype "power_in"))
      (node (ref "U18") (pin "20") (pinfunction "VCC_20") (pintype "passive"))
      (node (ref "U19") (pin "14") (pinfunction "VCC_14") (pintype "power_in"))
      (node (ref "U2") (pin "28") (pinfunction "VCC_28") (pintype "power_in"))
      (node (ref "U20") (pin "16") (pinfunction "VCC_16") (pintype "power_in"))
      (node (ref "U21") (pin "14") (pinfunction "VCC_14") (pintype "power_in"))
      (node (ref "U22") (pin "14") (pinfunction "VCC_14") (pintype "power_in"))
      (node (ref "U23") (pin "14") (pinfunction "VCC_14") (pintype "power_in"))
      (node (ref "U24") (pin "16") (pinfunction "VCC_16") (pintype "power_in"))
      (node (ref "U25") (pin "16") (pinfunction "VCC_16") (pintype "power_in"))
      (node (ref "U26") (pin "14") (pinfunction "VCC_14") (pintype "power_in"))
      (node (ref "U28") (pin "1") (pinfunction "VDD_1") (pintype "passive"))
      (node (ref "U3") (pin "1") (pinfunction "VPP_1") (pintype "passive"))
      (node (ref "U3") (pin "32") (pinfunction "VCC_32") (pintype "passive"))
      (node (ref "U5") (pin "20") (pinfunction "VCC_20") (pintype "power_in"))
      (node (ref "U6") (pin "16") (pinfunction "VCC_16") (pintype "power_in"))
      (node (ref "U7") (pin "16") (pinfunction "VCC_16") (pintype "power_in"))
      (node (ref "U8") (pin "16") (pinfunction "VCC_16") (pintype "power_in"))
      (node (ref "U8") (pin "6") (pinfunction "G1_6") (pintype "input"))
      (node (ref "U9") (pin "14") (pinfunction "VCC_14") (pintype "power_in"))
      (node (ref "Y2") (pin "4") (pinfunction "VCC_4") (pintype "bidirectional"))
    )
    (net (code "4") (name "12V") (class "Default")
      (node (ref "C29") (pin "1") (pinfunction "1_1") (pintype "passive"))
      (node (ref "C31") (pin "1") (pinfunction "1_1") (pintype "passive"))
      (node (ref "C32") (pin "2") (pinfunction "2_2") (pintype "passive"))
      (node (ref "C33") (pin "1") (pinfunction "1_1") (pintype "passive"))
      (node (ref "C85") (pin "+") (pinfunction "+_+") (pintype "passive"))
      (node (ref "C89") (pin "1") (pinfunction "1_1") (pintype "passive"))
      (node (ref "C95") (pin "1") (pinfunction "+_1") (pintype "passive"))
      (node (ref "L2") (pin "2") (pinfunction "2_2") (pintype "passive"))
      (node (ref "R54") (pin "1") (pinfunction "1_1") (pintype "passive"))
      (node (ref "R90") (pin "2") (pinfunction "2_2") (pintype "passive"))
      (node (ref "U29") (pin "4") (pinfunction "V+_4") (pintype "power_in"))
      (node (ref "U31") (pin "11") (pinfunction "VCC_11") (pintype "power_in"))
      (node (ref "U32") (pin "4") (pinfunction "V+_4") (pintype "power_in"))
      (node (ref "U33") (pin "4") (pinfunction "V+_4") (pintype "power_in"))
      (node (ref "VR1") (pin "1") (pinfunction "IN_1") (pintype "input"))
    )
    (net (code "5") (name "A0") (class "Default")
      (node (ref "U14") (pin "4") (pinfunction "A0_4") (pintype "passive"))
      (node (ref "U2") (pin "10") (pinfunction "A0_10") (pintype "input"))
      (node (ref "U3") (pin "12") (pinfunction "A0_12") (pintype "passive"))
      (node (ref "U4") (pin "8") (pinfunction "A0_8") (pintype "passive"))
    )
    (net (code "6") (name "A1") (class "Default")
      (node (ref "U2") (pin "9") (pinfunction "A1_9") (pintype "input"))
      (node (ref "U3") (pin "11") (pinfunction "A1_11") (pintype "passive"))
      (node (ref "U4") (pin "9") (pinfunction "A1_9") (pintype "passive"))
    )
    (net (code "7") (name "A2") (class "Default")
      (node (ref "U2") (pin "8") (pinfunction "A2_8") (pintype "input"))
      (node (ref "U3") (pin "10") (pinfunction "A2_10") (pintype "passive"))
      (node (ref "U4") (pin "10") (pinfunction "A2_10") (pintype "passive"))
    )
    (net (code "8") (name "A3") (class "Default")
      (node (ref "U2") (pin "7") (pinfunction "A3_7") (pintype "input"))
      (node (ref "U3") (pin "9") (pinfunction "A3_9") (pintype "passive"))
      (node (ref "U4") (pin "11") (pinfunction "A3_11") (pintype "passive"))
    )
    (net (code "9") (name "A4") (class "Default")
      (node (ref "U2") (pin "6") (pinfunction "A4_6") (pintype "input"))
      (node (ref "U3") (pin "8") (pinfunction "A4_8") (pintype "passive"))
      (node (ref "U4") (pin "12") (pinfunction "A4_12") (pintype "passive"))
    )
    (net (code "10") (name "A5") (class "Default")
      (node (ref "U2") (pin "5") (pinfunction "A5_5") (pintype "input"))
      (node (ref "U3") (pin "7") (pinfunction "A5_7") (pintype "passive"))
      (node (ref "U4") (pin "13") (pinfunction "A5_13") (pintype "passive"))
    )
    (net (code "11") (name "A6") (class "Default")
      (node (ref "U2") (pin "4") (pinfunction "A6_4") (pintype "input"))
      (node (ref "U3") (pin "6") (pinfunction "A6_6") (pintype "passive"))
      (node (ref "U4") (pin "14") (pinfunction "A6_14") (pintype "passive"))
    )
    (net (code "12") (name "A7") (class "Default")
      (node (ref "U2") (pin "3") (pinfunction "A7_3") (pintype "input"))
      (node (ref "U3") (pin "5") (pinfunction "A7_5") (pintype "passive"))
      (node (ref "U4") (pin "15") (pinfunction "A7_15") (pintype "passive"))
    )
    (net (code "13") (name "A8") (class "Default")
      (node (ref "U2") (pin "25") (pinfunction "A8_25") (pintype "input"))
      (node (ref "U3") (pin "27") (pinfunction "A8_27") (pintype "passive"))
      (node (ref "U4") (pin "16") (pinfunction "A8_16") (pintype "passive"))
    )
    (net (code "14") (name "A9") (class "Default")
      (node (ref "U2") (pin "24") (pinfunction "A9_24") (pintype "input"))
      (node (ref "U3") (pin "26") (pinfunction "A9_26") (pintype "passive"))
      (node (ref "U4") (pin "17") (pinfunction "A9_17") (pintype "passive"))
    )
    (net (code "15") (name "A10") (class "Default")
      (node (ref "U2") (pin "21") (pinfunction "A10_21") (pintype "input"))
      (node (ref "U3") (pin "23") (pinfunction "A10_23") (pintype "passive"))
      (node (ref "U4") (pin "18") (pinfunction "A10_18") (pintype "passive"))
      (node (ref "U8") (pin "1") (pinfunction "A_1") (pintype "input"))
    )
    (net (code "16") (name "A11") (class "Default")
      (node (ref "U2") (pin "23") (pinfunction "A11_23") (pintype "input"))
      (node (ref "U3") (pin "25") (pinfunction "A11_25") (pintype "passive"))
      (node (ref "U4") (pin "19") (pinfunction "A11_19") (pintype "passive"))
      (node (ref "U8") (pin "2") (pinfunction "B_2") (pintype "input"))
    )
    (net (code "17") (name "A12") (class "Default")
      (node (ref "U2") (pin "2") (pinfunction "A12_2") (pintype "input"))
      (node (ref "U3") (pin "4") (pinfunction "A12_4") (pintype "passive"))
      (node (ref "U4") (pin "20") (pinfunction "A12_20") (pintype "passive"))
      (node (ref "U8") (pin "3") (pinfunction "C_3") (pintype "input"))
    )
    (net (code "18") (name "A13") (class "Default")
      (node (ref "U20") (pin "14") (pinfunction "A_14") (pintype "input"))
      (node (ref "U3") (pin "28") (pinfunction "A13_28") (pintype "passive"))
      (node (ref "U4") (pin "21") (pinfunction "A13_21") (pintype "passive"))
    )
    (net (code "19") (name "A14") (class "Default")
      (node (ref "U20") (pin "2") (pinfunction "A_2") (pintype "input"))
      (node (ref "U4") (pin "22") (pinfunction "A14_22") (pintype "passive"))
    )
    (net (code "20") (name "A15") (class "Default")
      (node (ref "U20") (pin "3") (pinfunction "B_3") (pintype "input"))
      (node (ref "U3") (pin "29") (pinfunction "A14_29") (pintype "passive"))
      (node (ref "U4") (pin "23") (pinfunction "A15_23") (pintype "passive"))
    )
    (net (code "21") (name "ADPCM") (class "Default")
      (node (ref "U1") (pin "4") (pinfunction "~{CS}_4") (pintype "passive"))
      (node (ref "U8") (pin "12") (pinfunction "Y3_12") (pintype "output"))
    )
    (net (code "22") (name "ADPCMCLK") (class "Default")
      (node (ref "U1") (pin "5") (pinfunction "XTAL_5") (pintype "passive"))
      (node (ref "U9") (pin "5") (pinfunction "Q_5") (pintype "output"))
    )
    (net (code "23") (name "AGND") (class "Default")
      (node (ref "C102") (pin "-") (pinfunction "-_-") (pintype "passive"))
      (node (ref "C29") (pin "2") (pinfunction "2_2") (pintype "passive"))
      (node (ref "C31") (pin "2") (pinfunction "2_2") (pintype "passive"))
      (node (ref "C32") (pin "1") (pinfunction "1_1") (pintype "passive"))
      (node (ref "C33") (pin "2") (pinfunction "2_2") (pintype "passive"))
      (node (ref "C48") (pin "2") (pinfunction "2_2") (pintype "passive"))
      (node (ref "C50") (pin "2") (pinfunction "2_2") (pintype "passive"))
      (node (ref "C51") (pin "2") (pinfunction "2_2") (pintype "passive"))
      (node (ref "C54") (pin "2") (pinfunction "2_2") (pintype "passive"))
      (node (ref "C56") (pin "2") (pinfunction "2_2") (pintype "passive"))
      (node (ref "C61") (pin "2") (pinfunction "2_2") (pintype "passive"))
      (node (ref "C63") (pin "-") (pinfunction "-_-") (pintype "passive"))
      (node (ref "C64") (pin "-") (pinfunction "-_-") (pintype "passive"))
      (node (ref "C65") (pin "1") (pinfunction "1_1") (pintype "passive"))
      (node (ref "C66") (pin "-") (pinfunction "-_-") (pintype "passive"))
      (node (ref "C69") (pin "2") (pinfunction "2_2") (pintype "passive"))
      (node (ref "C73") (pin "-") (pinfunction "-_-") (pintype "passive"))
      (node (ref "C76") (pin "2") (pinfunction "2_2") (pintype "passive"))
      (node (ref "C80") (pin "-") (pinfunction "-_-") (pintype "passive"))
      (node (ref "C83") (pin "-") (pinfunction "-_-") (pintype "passive"))
      (node (ref "C84") (pin "-") (pinfunction "-_-") (pintype "passive"))
      (node (ref "C85") (pin "-") (pinfunction "-_-") (pintype "passive"))
      (node (ref "C88") (pin "2") (pinfunction "2_2") (pintype "passive"))
      (node (ref "C89") (pin "2") (pinfunction "2_2") (pintype "passive"))
      (node (ref "C90") (pin "1") (pinfunction "1_1") (pintype "passive"))
      (node (ref "C91") (pin "1") (pinfunction "1_1") (pintype "passive"))
      (node (ref "C95") (pin "2") (pinfunction "-_2") (pintype "passive"))
      (node (ref "C97") (pin "1") (pinfunction "1_1") (pintype "passive"))
      (node (ref "C98") (pin "2") (pinfunction "2_2") (pintype "passive"))
      (node (ref "CR2") (pin "1") (pinfunction "A_1") (pintype "passive"))
      (node (ref "R33") (pin "1") (pinfunction "1_1") (pintype "passive"))
      (node (ref "R41") (pin "1") (pinfunction "1_1") (pintype "passive"))
      (node (ref "R59") (pin "1") (pinfunction "1_1") (pintype "passive"))
      (node (ref "R60") (pin "1") (pinfunction "1_1") (pintype "passive"))
      (node (ref "R61") (pin "1") (pinfunction "1_1") (pintype "passive"))
      (node (ref "R68") (pin "1") (pinfunction "1_1") (pintype "passive"))
      (node (ref "R70") (pin "2") (pinfunction "2_2") (pintype "passive"))
      (node (ref "RV1") (pin "1") (pinfunction "A_1") (pintype "passive"))
      (node (ref "RV1") (pin "2") (pinfunction "S_2") (pintype "passive"))
      (node (ref "U15") (pin "2") (pinfunction "OUT2_2") (pintype "passive"))
      (node (ref "U28") (pin "16") (pinfunction "AGND-16_16") (pintype "passive"))
      (node (ref "U28") (pin "8") (pinfunction "AGND-8_8") (pintype "passive"))
      (node (ref "U29") (pin "11") (pinfunction "V-_11") (pintype "power_in"))
      (node (ref "U30") (pin "3") (pinfunction "GND_3") (pintype "power_in"))
      (node (ref "U31") (pin "3") (pinfunction "GND_IN_3") (pintype "power_in"))
      (node (ref "U31") (pin "7") (pinfunction "GND_OUT_7") (pintype "passive"))
      (node (ref "U32") (pin "11") (pinfunction "V-_11") (pintype "power_in"))
      (node (ref "U33") (pin "11") (pinfunction "V-_11") (pintype "power_in"))
      (node (ref "VR1") (pin "2") (pinfunction "REF_2") (pintype "passive"))
      (node (ref "W8") (pin "2") (pinfunction "2_2") (pintype "passive"))
    )
    (net (code "24") (name "ATE1") (class "Default")
      (node (ref "R25") (pin "1") (pinfunction "1_1") (pintype "passive"))
      (node (ref "U16") (pin "13") (pinfunction "5D_13") (pintype "input"))
      (node (ref "U16") (pin "14") (pinfunction "6D_14") (pintype "input"))
      (node (ref "U16") (pin "17") (pinfunction "7D_17") (pintype "input"))
      (node (ref "U16") (pin "18") (pinfunction "8D_18") (pintype "input"))
      (node (ref "U17") (pin "11") (pinfunction "D4_11") (pintype "input"))
      (node (ref "U17") (pin "13") (pinfunction "D5_13") (pintype "input"))
      (node (ref "U17") (pin "3") (pinfunction "D1_3") (pintype "input"))
      (node (ref "U18") (pin "8") (pinfunction "8-IN_8") (pintype "passive"))
      (node (ref "U19") (pin "9") (pinfunction "I0_9") (pintype "input"))
      (node (ref "U23") (pin "13") (pinfunction "CLR_13") (pintype "input"))
      (node (ref "U24") (pin "4") (pinfunction "EN_4") (pintype "bidirectional"))
      (node (ref "U24") (pin "9") (pinfunction "INC_9") (pintype "input"))
      (node (ref "U25") (pin "4") (pinfunction "EN_4") (pintype "bidirectional"))
      (node (ref "U9") (pin "10") (pinfunction "PRE_10") (pintype "input"))
      (node (ref "U9") (pin "12") (pinfunction "D_12") (pintype "input"))
    )
    (net (code "25") (name "ATE_CLR") (class "Default")
      (node (ref "R9") (pin "1") (pinfunction "1_1") (pintype "passive"))
      (node (ref "U17") (pin "1") (pinfunction "CLR_1") (pintype "input"))
      (node (ref "U22") (pin "1") (pinfunction "CLR_1") (pintype "input"))
      (node (ref "U22") (pin "13") (pinfunction "CLR_13") (pintype "input"))
      (node (ref "U23") (pin "1") (pinfunction "CLR_1") (pintype "input"))
      (node (ref "U9") (pin "1") (pinfunction "CLR_1") (pintype "input"))
    )
    (net (code "26") (name "BS0") (class "Default")
      (node (ref "U17") (pin "5") (pinfunction "Q2_5") (pintype "output"))
      (node (ref "U18") (pin "1") (pinfunction "1-IN_1") (pintype "passive"))
    )
    (net (code "27") (name "BS1") (class "Default")
      (node (ref "U17") (pin "15") (pinfunction "Q6_15") (pintype "output"))
      (node (ref "U18") (pin "2") (pinfunction "2-IN_2") (pintype "passive"))
    )
    (net (code "28") (name "BS2") (class "Default")
      (node (ref "U17") (pin "7") (pinfunction "Q3_7") (pintype "output"))
      (node (ref "U18") (pin "3") (pinfunction "3-IN_3") (pintype "passive"))
      (node (ref "U19") (pin "10") (pinfunction "I1_10") (pintype "input"))
    )
    (net (code "29") (name "B_SND_RD") (class "Default")
      (node (ref "C44") (pin "1") (pinfunction "1_1") (pintype "passive"))
      (node (ref "P1") (pin "15") (pinfunction "15_15") (pintype "passive"))
      (node (ref "R20") (pin "2") (pinfunction "2_2") (pintype "passive"))
    )
    (net (code "30") (name "B_VIDDAV") (class "Default")
      (node (ref "C104") (pin "2") (pinfunction "2_2") (pintype "passive"))
      (node (ref "R96") (pin "1") (pinfunction "1_1") (pintype "passive"))
      (node (ref "U25") (pin "14") (pinfunction "IND_14") (pintype "bidirectional"))
    )
    (net (code "31") (name "B_VIDRES") (class "Default")
      (node (ref "C106") (pin "1") (pinfunction "1_1") (pintype "passive"))
      (node (ref "R85") (pin "1") (pinfunction "1_1") (pintype "passive"))
      (node (ref "R93") (pin "1") (pinfunction "1_1") (pintype "passive"))
      (node (ref "U25") (pin "6") (pinfunction "INB_6") (pintype "bidirectional"))
    )
    (net (code "32") (name "D0") (class "Default")
      (node (ref "U1") (pin "37") (pinfunction "D0_37") (pintype "passive"))
      (node (ref "U14") (pin "10") (pinfunction "D0_10") (pintype "passive"))
      (node (ref "U15") (pin "11") (pinfunction "D0_11") (pintype "input"))
      (node (ref "U16") (pin "3") (pinfunction "1D_3") (pintype "input"))
      (node (ref "U17") (pin "4") (pinfunction "D2_4") (pintype "input"))
      (node (ref "U2") (pin "11") (pinfunction "I/O0_11") (pintype "bidirectional"))
      (node (ref "U3") (pin "13") (pinfunction "D0_13") (pintype "passive"))
      (node (ref "U4") (pin "31") (pinfunction "D0_31") (pintype "passive"))
      (node (ref "U5") (pin "3") (pinfunction "1D_3") (pintype "input"))
      (node (ref "U6") (pin "3") (pinfunction "OUTA_3") (pintype "bidirectional"))
    )
    (net (code "33") (name "D1") (class "Default")
      (node (ref "U1") (pin "38") (pinfunction "D1_38") (pintype "passive"))
      (node (ref "U14") (pin "12") (pinfunction "D1_12") (pintype "passive"))
      (node (ref "U15") (pin "10") (pinfunction "D1_10") (pintype "input"))
      (node (ref "U16") (pin "4") (pinfunction "2D_4") (pintype "input"))
      (node (ref "U17") (pin "14") (pinfunction "D6_14") (pintype "input"))
      (node (ref "U2") (pin "12") (pinfunction "I/O1_12") (pintype "bidirectional"))
      (node (ref "U3") (pin "14") (pinfunction "D1_14") (pintype "passive"))
      (node (ref "U4") (pin "30") (pinfunction "D1_30") (pintype "passive"))
      (node (ref "U5") (pin "4") (pinfunction "2D_4") (pintype "input"))
      (node (ref "U6") (pin "5") (pinfunction "OUTB_5") (pintype "bidirectional"))
    )
    (net (code "34") (name "D2") (class "Default")
      (node (ref "U1") (pin "39") (pinfunction "D2_39") (pintype "passive"))
      (node (ref "U14") (pin "13") (pinfunction "D2_13") (pintype "passive"))
      (node (ref "U15") (pin "9") (pinfunction "D2_9") (pintype "input"))
      (node (ref "U16") (pin "7") (pinfunction "3D_7") (pintype "input"))
      (node (ref "U17") (pin "6") (pinfunction "D3_6") (pintype "input"))
      (node (ref "U2") (pin "13") (pinfunction "I/O2_13") (pintype "bidirectional"))
      (node (ref "U3") (pin "15") (pinfunction "D2_15") (pintype "passive"))
      (node (ref "U4") (pin "29") (pinfunction "D2_29") (pintype "passive"))
      (node (ref "U5") (pin "7") (pinfunction "3D_7") (pintype "input"))
      (node (ref "U6") (pin "11") (pinfunction "OUTC_11") (pintype "bidirectional"))
    )
    (net (code "35") (name "D3") (class "Default")
      (node (ref "U1") (pin "40") (pinfunction "D3_40") (pintype "passive"))
      (node (ref "U14") (pin "14") (pinfunction "D3_14") (pintype "passive"))
      (node (ref "U15") (pin "8") (pinfunction "D3_8") (pintype "input"))
      (node (ref "U16") (pin "8") (pinfunction "4D_8") (pintype "input"))
      (node (ref "U2") (pin "15") (pinfunction "I/O3_15") (pintype "bidirectional"))
      (node (ref "U3") (pin "17") (pinfunction "D3_17") (pintype "passive"))
      (node (ref "U4") (pin "28") (pinfunction "D3_28") (pintype "passive"))
      (node (ref "U5") (pin "8") (pinfunction "4D_8") (pintype "input"))
      (node (ref "U6") (pin "13") (pinfunction "OUTD_13") (pintype "bidirectional"))
    )
    (net (code "36") (name "D4") (class "Default")
      (node (ref "U1") (pin "41") (pinfunction "D4_41") (pintype "passive"))
      (node (ref "U10") (pin "3") (pinfunction "OUTA_3") (pintype "bidirectional"))
      (node (ref "U14") (pin "15") (pinfunction "D4_15") (pintype "passive"))
      (node (ref "U15") (pin "7") (pinfunction "D4_7") (pintype "input"))
      (node (ref "U2") (pin "16") (pinfunction "I/O4_16") (pintype "bidirectional"))
      (node (ref "U3") (pin "18") (pinfunction "D4_18") (pintype "passive"))
      (node (ref "U4") (pin "27") (pinfunction "D4_27") (pintype "passive"))
      (node (ref "U5") (pin "13") (pinfunction "5D_13") (pintype "input"))
    )
    (net (code "37") (name "D5") (class "Default")
      (node (ref "U1") (pin "42") (pinfunction "D5_42") (pintype "passive"))
      (node (ref "U10") (pin "5") (pinfunction "OUTB_5") (pintype "bidirectional"))
      (node (ref "U14") (pin "16") (pinfunction "D5_16") (pintype "passive"))
      (node (ref "U15") (pin "6") (pinfunction "D5_6") (pintype "input"))
      (node (ref "U2") (pin "17") (pinfunction "I/O5_17") (pintype "bidirectional"))
      (node (ref "U3") (pin "19") (pinfunction "D5_19") (pintype "passive"))
      (node (ref "U4") (pin "26") (pinfunction "D5_26") (pintype "passive"))
      (node (ref "U5") (pin "14") (pinfunction "6D_14") (pintype "input"))
    )
    (net (code "38") (name "D6") (class "Default")
      (node (ref "U1") (pin "43") (pinfunction "D6_43") (pintype "passive"))
      (node (ref "U10") (pin "11") (pinfunction "OUTC_11") (pintype "bidirectional"))
      (node (ref "U14") (pin "17") (pinfunction "D6_17") (pintype "passive"))
      (node (ref "U15") (pin "5") (pinfunction "D6_5") (pintype "input"))
      (node (ref "U2") (pin "18") (pinfunction "I/O6_18") (pintype "bidirectional"))
      (node (ref "U3") (pin "20") (pinfunction "D6_20") (pintype "passive"))
      (node (ref "U4") (pin "25") (pinfunction "D6_25") (pintype "passive"))
      (node (ref "U5") (pin "17") (pinfunction "7D_17") (pintype "input"))
    )
    (net (code "39") (name "D7") (class "Default")
      (node (ref "U1") (pin "44") (pinfunction "D7_44") (pintype "passive"))
      (node (ref "U10") (pin "13") (pinfunction "OUTD_13") (pintype "bidirectional"))
      (node (ref "U14") (pin "18") (pinfunction "D7_18") (pintype "passive"))
      (node (ref "U15") (pin "4") (pinfunction "D7_4") (pintype "input"))
      (node (ref "U2") (pin "19") (pinfunction "I/O7_19") (pintype "bidirectional"))
      (node (ref "U3") (pin "21") (pinfunction "D7_21") (pintype "passive"))
      (node (ref "U4") (pin "24") (pinfunction "D7_24") (pintype "passive"))
      (node (ref "U5") (pin "18") (pinfunction "8D_18") (pintype "input"))
    )
    (net (code "40") (name "DAC") (class "Default")
      (node (ref "U15") (pin "12") (pinfunction "~{CS}_12") (pintype "input"))
      (node (ref "U8") (pin "13") (pinfunction "Y2_13") (pintype "output"))
    )
    (net (code "41") (name "DAC-OUT") (class "Default")
      (node (ref "R61") (pin "2") (pinfunction "2_2") (pintype "passive"))
      (node (ref "R62") (pin "2") (pinfunction "2_2") (pintype "passive"))
      (node (ref "U29") (pin "8") (pinfunction "OUT_8") (pintype "output"))
      (node (ref "U29") (pin "9") (pinfunction "-IN_9") (pintype "input"))
    )
    (net (code "42") (name "FFO") (class "Default")
      (node (ref "U24") (pin "1") (pinfunction "INA_1") (pintype "input"))
      (node (ref "U9") (pin "9") (pinfunction "Q_9") (pintype "output"))
    )
    (net (code "43") (name "FIRQ") (class "Default")
      (node (ref "R7") (pin "1") (pinfunction "1_1") (pintype "passive"))
      (node (ref "U14") (pin "2") (pinfunction "~{IRQ}_2") (pintype "passive"))
      (node (ref "U4") (pin "4") (pinfunction "~{FIRQ}_4") (pintype "passive"))
    )
    (net (code "44") (name "GND") (class "Default")
      (node (ref "C10") (pin "2") (pinfunction "2_2") (pintype "passive"))
      (node (ref "C100") (pin "-") (pinfunction "-_-") (pintype "passive"))
      (node (ref "C103") (pin "-") (pinfunction "-_-") (pintype "passive"))
      (node (ref "C104") (pin "1") (pinfunction "1_1") (pintype "passive"))
      (node (ref "C105") (pin "1") (pinfunction "1_1") (pintype "passive"))
      (node (ref "C106") (pin "2") (pinfunction "2_2") (pintype "passive"))
      (node (ref "C107") (pin "2") (pinfunction "2_2") (pintype "passive"))
      (node (ref "C11") (pin "2") (pinfunction "2_2") (pintype "passive"))
      (node (ref "C12") (pin "2") (pinfunction "2_2") (pintype "passive"))
      (node (ref "C13") (pin "2") (pinfunction "2_2") (pintype "passive"))
      (node (ref "C14") (pin "2") (pinfunction "2_2") (pintype "passive"))
      (node (ref "C15") (pin "2") (pinfunction "2_2") (pintype "passive"))
      (node (ref "C16") (pin "2") (pinfunction "2_2") (pintype "passive"))
      (node (ref "C17") (pin "2") (pinfunction "2_2") (pintype "passive"))
      (node (ref "C18") (pin "2") (pinfunction "2_2") (pintype "passive"))
      (node (ref "C19") (pin "2") (pinfunction "2_2") (pintype "passive"))
      (node (ref "C2") (pin "2") (pinfunction "2_2") (pintype "passive"))
      (node (ref "C20") (pin "2") (pinfunction "2_2") (pintype "passive"))
      (node (ref "C21") (pin "2") (pinfunction "2_2") (pintype "passive"))
      (node (ref "C22") (pin "2") (pinfunction "2_2") (pintype "passive"))
      (node (ref "C23") (pin "2") (pinfunction "2_2") (pintype "passive"))
      (node (ref "C24") (pin "2") (pinfunction "2_2") (pintype "passive"))
      (node (ref "C25") (pin "2") (pinfunction "2_2") (pintype "passive"))
      (node (ref "C26") (pin "2") (pinfunction "2_2") (pintype "passive"))
      (node (ref "C28") (pin "2") (pinfunction "2_2") (pintype "passive"))
      (node (ref "C3") (pin "2") (pinfunction "2_2") (pintype "passive"))
      (node (ref "C35") (pin "2") (pinfunction "2_2") (pintype "passive"))
      (node (ref "C36") (pin "2") (pinfunction "2_2") (pintype "passive"))
      (node (ref "C37") (pin "2") (pinfunction "2_2") (pintype "passive"))
      (node (ref "C38") (pin "2") (pinfunction "2_2") (pintype "passive"))
      (node (ref "C39") (pin "2") (pinfunction "2_2") (pintype "passive"))
      (node (ref "C4") (pin "2") (pinfunction "2_2") (pintype "passive"))
      (node (ref "C40") (pin "2") (pinfunction "2_2") (pintype "passive"))
      (node (ref "C41") (pin "2") (pinfunction "2_2") (pintype "passive"))
      (node (ref "C42") (pin "2") (pinfunction "2_2") (pintype "passive"))
      (node (ref "C43") (pin "2") (pinfunction "2_2") (pintype "passive"))
      (node (ref "C44") (pin "2") (pinfunction "2_2") (pintype "passive"))
      (node (ref "C45") (pin "2") (pinfunction "2_2") (pintype "passive"))
      (node (ref "C49") (pin "2") (pinfunction "2_2") (pintype "passive"))
      (node (ref "C5") (pin "2") (pinfunction "2_2") (pintype "passive"))
      (node (ref "C6") (pin "2") (pinfunction "2_2") (pintype "passive"))
      (node (ref "C7") (pin "2") (pinfunction "2_2") (pintype "passive"))
      (node (ref "C70") (pin "-") (pinfunction "-_-") (pintype "passive"))
      (node (ref "C72") (pin "2") (pinfunction "2_2") (pintype "passive"))
      (node (ref "C74") (pin "2") (pinfunction "2_2") (pintype "passive"))
      (node (ref "C8") (pin "2") (pinfunction "2_2") (pintype "passive"))
      (node (ref "C9") (pin "2") (pinfunction "2_2") (pintype "passive"))
      (node (ref "C99") (pin "2") (pinfunction "2_2") (pintype "passive"))
      (node (ref "MTG1") (pin "P1") (pinfunction "P$1_P1") (pintype "bidirectional"))
      (node (ref "MTG2") (pin "P1") (pinfunction "P$1_P1") (pintype "bidirectional"))
      (node (ref "MTG3") (pin "P1") (pinfunction "P$1_P1") (pintype "bidirectional"))
      (node (ref "MTG4") (pin "P1") (pinfunction "P$1_P1") (pintype "bidirectional"))
      (node (ref "P1") (pin "1") (pinfunction "1_1") (pintype "passive"))
      (node (ref "P6") (pin "2") (pinfunction "2_2") (pintype "passive"))
      (node (ref "Q1") (pin "2") (pinfunction "E_2") (pintype "passive"))
      (node (ref "R4") (pin "2") (pinfunction "2_2") (pintype "passive"))
      (node (ref "R83") (pin "1") (pinfunction "1_1") (pintype "passive"))
      (node (ref "U1") (pin "1") (pinfunction "VSS_1") (pintype "passive"))
      (node (ref "U10") (pin "4") (pinfunction "EN_4") (pintype "bidirectional"))
      (node (ref "U10") (pin "8") (pinfunction "GND_8") (pintype "power_in"))
      (node (ref "U11") (pin "4") (pinfunction "EN_4") (pintype "bidirectional"))
      (node (ref "U11") (pin "8") (pinfunction "GND_8") (pintype "power_in"))
      (node (ref "U12") (pin "16") (pinfunction "VSS_16") (pintype "passive"))
      (node (ref "U12") (pin "22") (pinfunction "~{CS}_22") (pintype "passive"))
      (node (ref "U13") (pin "16") (pinfunction "VSS_16") (pintype "passive"))
      (node (ref "U13") (pin "22") (pinfunction "~{CS}_22") (pintype "passive"))
      (node (ref "U14") (pin "1") (pinfunction "VSS-1_1") (pintype "passive"))
      (node (ref "U14") (pin "11") (pinfunction "VSS-11_11") (pintype "passive"))
      (node (ref "U15") (pin "3") (pinfunction "GND_3") (pintype "power_in"))
      (node (ref "U16") (pin "10") (pinfunction "GND_10") (pintype "power_in"))
      (node (ref "U17") (pin "8") (pinfunction "GND_8") (pintype "power_in"))
      (node (ref "U18") (pin "10") (pinfunction "VSS_10") (pintype "passive"))
      (node (ref "U19") (pin "7") (pinfunction "GND_7") (pintype "power_in"))
      (node (ref "U2") (pin "14") (pinfunction "VSS_14") (pintype "power_in"))
      (node (ref "U20") (pin "13") (pinfunction "B_13") (pintype "input"))
      (node (ref "U20") (pin "8") (pinfunction "GND_8") (pintype "power_in"))
      (node (ref "U21") (pin "7") (pinfunction "GND_7") (pintype "power_in"))
      (node (ref "U22") (pin "7") (pinfunction "GND_7") (pintype "power_in"))
      (node (ref "U23") (pin "7") (pinfunction "GND_7") (pintype "power_in"))
      (node (ref "U24") (pin "8") (pinfunction "GND_8") (pintype "power_in"))
      (node (ref "U25") (pin "8") (pinfunction "GND_8") (pintype "power_in"))
      (node (ref "U26") (pin "7") (pinfunction "GND_7") (pintype "power_in"))
      (node (ref "U28") (pin "3") (pinfunction "VSS_3") (pintype "passive"))
      (node (ref "U3") (pin "16") (pinfunction "VSS_16") (pintype "passive"))
      (node (ref "U3") (pin "22") (pinfunction "~{CS}_22") (pintype "passive"))
      (node (ref "U4") (pin "1") (pinfunction "VSS_1") (pintype "passive"))
      (node (ref "U4") (pin "39") (pinfunction "TSC_39") (pintype "passive"))
      (node (ref "U5") (pin "10") (pinfunction "GND_10") (pintype "power_in"))
      (node (ref "U6") (pin "4") (pinfunction "EN_4") (pintype "bidirectional"))
      (node (ref "U6") (pin "8") (pinfunction "GND_8") (pintype "power_in"))
      (node (ref "U7") (pin "4") (pinfunction "EN_4") (pintype "bidirectional"))
      (node (ref "U7") (pin "8") (pinfunction "GND_8") (pintype "power_in"))
      (node (ref "U8") (pin "8") (pinfunction "GND_8") (pintype "power_in"))
      (node (ref "U9") (pin "7") (pinfunction "GND_7") (pintype "power_in"))
      (node (ref "W8") (pin "1") (pinfunction "1_1") (pintype "passive"))
      (node (ref "Y2") (pin "2") (pinfunction "GND_2") (pintype "bidirectional"))
    )
    (net (code "45") (name "IRQ") (class "Default")
      (node (ref "R5") (pin "1") (pinfunction "1_1") (pintype "passive"))
      (node (ref "U23") (pin "9") (pinfunction "Q_9") (pintype "output"))
      (node (ref "U24") (pin "15") (pinfunction "IND_15") (pintype "input"))
      (node (ref "U4") (pin "3") (pinfunction "~{IRQ}_3") (pintype "passive"))
    )
    (net (code "46") (name "Net-(C47-Pad1)") (class "Default")
      (node (ref "C47") (pin "1") (pinfunction "1_1") (pintype "passive"))
      (node (ref "Y1") (pin "2") (pinfunction "2_2") (pintype "passive"))
    )
    (net (code "47") (name "Net-(C52-Pad2)") (class "Default")
      (node (ref "C52") (pin "2") (pinfunction "2_2") (pintype "passive"))
      (node (ref "R38") (pin "2") (pinfunction "2_2") (pintype "passive"))
      (node (ref "R39") (pin "1") (pinfunction "1_1") (pintype "passive"))
    )
    (net (code "48") (name "Net-(C54-Pad1)") (class "Default")
      (node (ref "C54") (pin "1") (pinfunction "1_1") (pintype "passive"))
      (node (ref "R44") (pin "1") (pinfunction "1_1") (pintype "passive"))
      (node (ref "R45") (pin "2") (pinfunction "2_2") (pintype "passive"))
      (node (ref "R46") (pin "2") (pinfunction "2_2") (pintype "passive"))
    )
    (net (code "49") (name "Net-(C58-Pad2)") (class "Default")
      (node (ref "C58") (pin "2") (pinfunction "2_2") (pintype "passive"))
      (node (ref "R35") (pin "1") (pinfunction "1_1") (pintype "passive"))
      (node (ref "R36") (pin "2") (pinfunction "2_2") (pintype "passive"))
    )
    (net (code "50") (name "Net-(C61-Pad1)") (class "Default")
      (node (ref "C61") (pin "1") (pinfunction "1_1") (pintype "passive"))
      (node (ref "R40") (pin "1") (pinfunction "1_1") (pintype "passive"))
      (node (ref "R51") (pin "2") (pinfunction "2_2") (pintype "passive"))
      (node (ref "R52") (pin "2") (pinfunction "2_2") (pintype "passive"))
    )
    (net (code "51") (name "Net-(C69-Pad1)") (class "Default")
      (node (ref "C69") (pin "1") (pinfunction "1_1") (pintype "passive"))
      (node (ref "R62") (pin "1") (pinfunction "1_1") (pintype "passive"))
      (node (ref "R63") (pin "2") (pinfunction "2_2") (pintype "passive"))
      (node (ref "R64") (pin "2") (pinfunction "2_2") (pintype "passive"))
    )
    (net (code "52") (name "Net-(C74-Pad1)") (class "Default")
      (node (ref "C74") (pin "1") (pinfunction "1_1") (pintype "passive"))
      (node (ref "L1") (pin "2") (pinfunction "2_2") (pintype "passive"))
      (node (ref "P6") (pin "1") (pinfunction "1_1") (pintype "passive"))
    )
    (net (code "53") (name "Net-(C81-Pad+)") (class "Default")
      (node (ref "C81") (pin "+") (pinfunction "+_+") (pintype "passive"))
      (node (ref "R70") (pin "1") (pinfunction "1_1") (pintype "passive"))
      (node (ref "R71") (pin "2") (pinfunction "2_2") (pintype "passive"))
    )
    (net (code "54") (name "Net-(C88-Pad1)") (class "Default")
      (node (ref "C88") (pin "1") (pinfunction "1_1") (pintype "passive"))
      (node (ref "L2") (pin "1") (pinfunction "1_1") (pintype "passive"))
      (node (ref "P6") (pin "5") (pinfunction "5_5") (pintype "passive"))
      (node (ref "P6") (pin "6") (pinfunction "6_6") (pintype "passive"))
    )
    (net (code "55") (name "Net-(CR1-PadC)") (class "Default")
      (node (ref "CR1") (pin "C") (pinfunction "C_C") (pintype "passive"))
      (node (ref "R30") (pin "1") (pinfunction "1_1") (pintype "passive"))
    )
    (net (code "56") (name "Net-(CR2-C)") (class "Default")
      (node (ref "C73") (pin "+") (pinfunction "+_+") (pintype "passive"))
      (node (ref "CR2") (pin "3") (pinfunction "C_3") (pintype "passive"))
      (node (ref "R54") (pin "2") (pinfunction "2_2") (pintype "passive"))
      (node (ref "U32") (pin "10") (pinfunction "+IN_10") (pintype "input"))
      (node (ref "U33") (pin "12") (pinfunction "+IN_12") (pintype "input"))
      (node (ref "U33") (pin "3") (pinfunction "+IN_3") (pintype "input"))
      (node (ref "U33") (pin "5") (pinfunction "+IN_5") (pintype "input"))
    )
    (net (code "57") (name "Net-(P1-Pad13)") (class "Default")
      (node (ref "P1") (pin "13") (pinfunction "13_13") (pintype "passive"))
      (node (ref "R96") (pin "2") (pinfunction "2_2") (pintype "passive"))
    )
    (net (code "58") (name "Net-(P1-Pad16)") (class "Default")
      (node (ref "P1") (pin "16") (pinfunction "16_16") (pintype "passive"))
      (node (ref "R95") (pin "2") (pinfunction "2_2") (pintype "passive"))
    )
    (net (code "59") (name "Net-(P1-Pad17)") (class "Default")
      (node (ref "P1") (pin "17") (pinfunction "17_17") (pintype "passive"))
      (node (ref "R93") (pin "2") (pinfunction "2_2") (pintype "passive"))
    )
    (net (code "60") (name "Net-(P1-Pad18)") (class "Default")
      (node (ref "P1") (pin "18") (pinfunction "18_18") (pintype "passive"))
      (node (ref "R94") (pin "2") (pinfunction "2_2") (pintype "passive"))
    )
    (net (code "61") (name "Net-(Q1-B)") (class "Default")
      (node (ref "C62") (pin "2") (pinfunction "2_2") (pintype "passive"))
      (node (ref "Q1") (pin "1") (pinfunction "B_1") (pintype "passive"))
      (node (ref "R28") (pin "2") (pinfunction "2_2") (pintype "passive"))
    )
    (net (code "62") (name "Net-(Q1-C)") (class "Default")
      (node (ref "Q1") (pin "3") (pinfunction "C_3") (pintype "passive"))
      (node (ref "R27") (pin "1") (pinfunction "1_1") (pintype "passive"))
      (node (ref "U4") (pin "34") (pinfunction "E_34") (pintype "passive"))
    )
    (net (code "63") (name "Net-(RV1-E)") (class "Default")
      (node (ref "R87") (pin "2") (pinfunction "2_2") (pintype "passive"))
      (node (ref "RV1") (pin "3") (pinfunction "E_3") (pintype "passive"))
    )
    (net (code "64") (name "Net-(U1-DAO)") (class "Default")
      (node (ref "C46") (pin "-") (pinfunction "-_-") (pintype "passive"))
      (node (ref "U1") (pin "36") (pinfunction "DAO_36") (pintype "passive"))
    )
    (net (code "65") (name "Net-(U1-VCC)") (class "Default")
      (node (ref "C103") (pin "+") (pinfunction "+_+") (pintype "passive"))
      (node (ref "C99") (pin "1") (pinfunction "1_1") (pintype "passive"))
      (node (ref "R89") (pin "1") (pinfunction "1_1") (pintype "passive"))
      (node (ref "U1") (pin "17") (pinfunction "VCC_17") (pintype "passive"))
    )
    (net (code "66") (name "Net-(U2-CS2)") (class "Default")
      (node (ref "R1") (pin "1") (pinfunction "1_1") (pintype "passive"))
      (node (ref "U2") (pin "26") (pinfunction "CS2_26") (pintype "input"))
    )
    (net (code "67") (name "Net-(U2-~{CS1})") (class "Default")
      (node (ref "U2") (pin "20") (pinfunction "~{CS1}_20") (pintype "input"))
      (node (ref "U20") (pin "12") (pinfunction "Y0_12") (pintype "output"))
    )
    (net (code "68") (name "Net-(U4-~{HALT})") (class "Default")
      (node (ref "R6") (pin "1") (pinfunction "1_1") (pintype "passive"))
      (node (ref "U4") (pin "40") (pinfunction "~{HALT}_40") (pintype "passive"))
    )
    (net (code "69") (name "Net-(U4-~{NMI})") (class "Default")
      (node (ref "R2") (pin "1") (pinfunction "1_1") (pintype "passive"))
      (node (ref "U4") (pin "2") (pinfunction "~{NMI}_2") (pintype "passive"))
    )
    (net (code "70") (name "Net-(U5A-1Q)") (class "Default")
      (node (ref "U5") (pin "2") (pinfunction "1Q_2") (pintype "tri_state"))
      (node (ref "U7") (pin "1") (pinfunction "INA_1") (pintype "input"))
    )
    (net (code "71") (name "Net-(U5A-2Q)") (class "Default")
      (node (ref "U5") (pin "5") (pinfunction "2Q_5") (pintype "tri_state"))
      (node (ref "U7") (pin "7") (pinfunction "INB_7") (pintype "input"))
    )
    (net (code "72") (name "Net-(U5A-3Q)") (class "Default")
      (node (ref "U5") (pin "6") (pinfunction "3Q_6") (pintype "tri_state"))
      (node (ref "U7") (pin "9") (pinfunction "INC_9") (pintype "input"))
    )
    (net (code "73") (name "Net-(U5A-4Q)") (class "Default")
      (node (ref "U5") (pin "9") (pinfunction "4Q_9") (pintype "tri_state"))
      (node (ref "U7") (pin "15") (pinfunction "IND_15") (pintype "input"))
    )
    (net (code "74") (name "Net-(U6-INA)") (class "Default")
      (node (ref "R11") (pin "1") (pinfunction "1_1") (pintype "passive"))
      (node (ref "U6") (pin "2") (pinfunction "INA_2") (pintype "bidirectional"))
      (node (ref "U7") (pin "2") (pinfunction "OUTA_2") (pintype "bidirectional"))
    )
    (net (code "75") (name "Net-(U6-INB)") (class "Default")
      (node (ref "R13") (pin "1") (pinfunction "1_1") (pintype "passive"))
      (node (ref "U6") (pin "6") (pinfunction "INB_6") (pintype "bidirectional"))
      (node (ref "U7") (pin "6") (pinfunction "OUTB_6") (pintype "bidirectional"))
    )
    (net (code "76") (name "Net-(U6-INC)") (class "Default")
      (node (ref "R14") (pin "1") (pinfunction "1_1") (pintype "passive"))
      (node (ref "U6") (pin "10") (pinfunction "INC_10") (pintype "bidirectional"))
      (node (ref "U7") (pin "10") (pinfunction "OUTC_10") (pintype "bidirectional"))
    )
    (net (code "77") (name "Net-(U6-IND)") (class "Default")
      (node (ref "R12") (pin "1") (pinfunction "1_1") (pintype "passive"))
      (node (ref "U6") (pin "14") (pinfunction "IND_14") (pintype "bidirectional"))
      (node (ref "U7") (pin "14") (pinfunction "OUTD_14") (pintype "bidirectional"))
    )
    (net (code "78") (name "Net-(U9A-D)") (class "Default")
      (node (ref "U9") (pin "2") (pinfunction "D_2") (pintype "input"))
      (node (ref "U9") (pin "6") (pinfunction "~{Q}_6") (pintype "output"))
    )
    (net (code "79") (name "Net-(U10-INA)") (class "Default")
      (node (ref "R15") (pin "1") (pinfunction "1_1") (pintype "passive"))
      (node (ref "U10") (pin "2") (pinfunction "INA_2") (pintype "bidirectional"))
      (node (ref "U11") (pin "2") (pinfunction "OUTA_2") (pintype "bidirectional"))
    )
    (net (code "80") (name "Net-(U10-INB)") (class "Default")
      (node (ref "R16") (pin "1") (pinfunction "1_1") (pintype "passive"))
      (node (ref "U10") (pin "6") (pinfunction "INB_6") (pintype "bidirectional"))
      (node (ref "U11") (pin "6") (pinfunction "OUTB_6") (pintype "bidirectional"))
    )
    (net (code "81") (name "Net-(U10-INC)") (class "Default")
      (node (ref "R17") (pin "1") (pinfunction "1_1") (pintype "passive"))
      (node (ref "U10") (pin "10") (pinfunction "INC_10") (pintype "bidirectional"))
      (node (ref "U11") (pin "10") (pinfunction "OUTC_10") (pintype "bidirectional"))
    )
    (net (code "82") (name "Net-(U10-IND)") (class "Default")
      (node (ref "R18") (pin "1") (pinfunction "1_1") (pintype "passive"))
      (node (ref "U10") (pin "14") (pinfunction "IND_14") (pintype "bidirectional"))
      (node (ref "U11") (pin "14") (pinfunction "OUTD_14") (pintype "bidirectional"))
    )
    (net (code "83") (name "Net-(U10-~{INA})") (class "Default")
      (node (ref "R82") (pin "1") (pinfunction "1_1") (pintype "passive"))
      (node (ref "R83") (pin "2") (pinfunction "2_2") (pintype "passive"))
      (node (ref "U10") (pin "1") (pinfunction "~{INA}_1") (pintype "bidirectional"))
      (node (ref "U10") (pin "15") (pinfunction "~{IND}_15") (pintype "bidirectional"))
      (node (ref "U10") (pin "7") (pinfunction "~{INB}_7") (pintype "bidirectional"))
      (node (ref "U10") (pin "9") (pinfunction "~{INC}_9") (pintype "bidirectional"))
      (node (ref "U25") (pin "1") (pinfunction "~{INA}_1") (pintype "bidirectional"))
      (node (ref "U25") (pin "15") (pinfunction "~{IND}_15") (pintype "bidirectional"))
      (node (ref "U25") (pin "7") (pinfunction "~{INB}_7") (pintype "bidirectional"))
      (node (ref "U25") (pin "9") (pinfunction "~{INC}_9") (pintype "bidirectional"))
      (node (ref "U6") (pin "1") (pinfunction "~{INA}_1") (pintype "bidirectional"))
      (node (ref "U6") (pin "15") (pinfunction "~{IND}_15") (pintype "bidirectional"))
      (node (ref "U6") (pin "7") (pinfunction "~{INB}_7") (pintype "bidirectional"))
      (node (ref "U6") (pin "9") (pinfunction "~{INC}_9") (pintype "bidirectional"))
    )
    (net (code "84") (name "Net-(U11-INA)") (class "Default")
      (node (ref "U11") (pin "1") (pinfunction "INA_1") (pintype "input"))
      (node (ref "U5") (pin "12") (pinfunction "5Q_12") (pintype "tri_state"))
    )
    (net (code "85") (name "Net-(U11-INB)") (class "Default")
      (node (ref "U11") (pin "7") (pinfunction "INB_7") (pintype "input"))
      (node (ref "U5") (pin "15") (pinfunction "6Q_15") (pintype "tri_state"))
    )
    (net (code "86") (name "Net-(U11-INC)") (class "Default")
      (node (ref "U11") (pin "9") (pinfunction "INC_9") (pintype "input"))
      (node (ref "U5") (pin "16") (pinfunction "7Q_16") (pintype "tri_state"))
    )
    (net (code "87") (name "Net-(U11-IND)") (class "Default")
      (node (ref "U11") (pin "15") (pinfunction "IND_15") (pintype "input"))
      (node (ref "U5") (pin "19") (pinfunction "8Q_19") (pintype "tri_state"))
    )
    (net (code "88") (name "Net-(U12-~{OE})") (class "Default")
      (node (ref "U12") (pin "24") (pinfunction "~{OE}_24") (pintype "passive"))
      (node (ref "U19") (pin "8") (pinfunction "O_8") (pintype "output"))
      (node (ref "U26") (pin "11") (pinfunction "I_11") (pintype "input"))
    )
    (net (code "89") (name "Net-(U13-~{OE})") (class "Default")
      (node (ref "U13") (pin "24") (pinfunction "~{OE}_24") (pintype "passive"))
      (node (ref "U26") (pin "10") (pinfunction "O_10") (pintype "output"))
    )
    (net (code "90") (name "Net-(U14-CLK)") (class "Default")
      (node (ref "U14") (pin "23") (pinfunction "CLK_23") (pintype "passive"))
      (node (ref "U28") (pin "2") (pinfunction "CLK_2") (pintype "passive"))
    )
    (net (code "91") (name "Net-(U14-OSC)") (class "Default")
      (node (ref "U14") (pin "24") (pinfunction "OSC_24") (pintype "passive"))
      (node (ref "U26") (pin "6") (pinfunction "O_6") (pintype "output"))
    )
    (net (code "92") (name "Net-(U14-SH1)") (class "Default")
      (node (ref "U14") (pin "20") (pinfunction "SH1_20") (pintype "passive"))
      (node (ref "U28") (pin "6") (pinfunction "SAM1_6") (pintype "passive"))
    )
    (net (code "93") (name "Net-(U14-SH2)") (class "Default")
      (node (ref "U14") (pin "19") (pinfunction "SH2_19") (pintype "passive"))
      (node (ref "U28") (pin "5") (pinfunction "SAM2_5") (pintype "passive"))
    )
    (net (code "94") (name "Net-(U14-SO)") (class "Default")
      (node (ref "U14") (pin "21") (pinfunction "SO_21") (pintype "passive"))
      (node (ref "U28") (pin "4") (pinfunction "SO_4") (pintype "passive"))
    )
    (net (code "95") (name "Net-(U15-OUT1)") (class "Default")
      (node (ref "C63") (pin "+") (pinfunction "+_+") (pintype "passive"))
      (node (ref "R68") (pin "2") (pinfunction "2_2") (pintype "passive"))
      (node (ref "R69") (pin "1") (pinfunction "1_1") (pintype "passive"))
      (node (ref "U15") (pin "1") (pinfunction "OUT1_1") (pintype "passive"))
    )
    (net (code "96") (name "Net-(U15-VREF)") (class "Default")
      (node (ref "C98") (pin "1") (pinfunction "1_1") (pintype "passive"))
      (node (ref "U15") (pin "15") (pinfunction "VREF_15") (pintype "input"))
      (node (ref "U29") (pin "12") (pinfunction "+IN_12") (pintype "input"))
    )
    (net (code "97") (name "Net-(U16A-1Q)") (class "Default")
      (node (ref "R24") (pin "1") (pinfunction "1_1") (pintype "passive"))
      (node (ref "U16") (pin "2") (pinfunction "1Q_2") (pintype "tri_state"))
      (node (ref "U3") (pin "3") (pinfunction "A15_3") (pintype "passive"))
    )
    (net (code "98") (name "Net-(U16A-2Q)") (class "Default")
      (node (ref "R23") (pin "1") (pinfunction "1_1") (pintype "passive"))
      (node (ref "U16") (pin "5") (pinfunction "2Q_5") (pintype "tri_state"))
      (node (ref "U3") (pin "2") (pinfunction "A16_2") (pintype "passive"))
    )
    (net (code "99") (name "Net-(U16A-3Q)") (class "Default")
      (node (ref "R22") (pin "1") (pinfunction "1_1") (pintype "passive"))
      (node (ref "U16") (pin "6") (pinfunction "3Q_6") (pintype "tri_state"))
      (node (ref "U3") (pin "30") (pinfunction "A17_30") (pintype "passive"))
    )
    (net (code "100") (name "Net-(U16A-4Q)") (class "Default")
      (node (ref "R26") (pin "1") (pinfunction "1_1") (pintype "passive"))
      (node (ref "U16") (pin "9") (pinfunction "4Q_9") (pintype "tri_state"))
      (node (ref "U3") (pin "31") (pinfunction "A18_31") (pintype "passive"))
    )
    (net (code "101") (name "Net-(U16A-CLK)") (class "Default")
      (node (ref "U16") (pin "11") (pinfunction "CLK_11") (pintype "input"))
      (node (ref "U26") (pin "8") (pinfunction "O_8") (pintype "output"))
    )
    (net (code "102") (name "Net-(U16A-OC)") (class "Default")
      (node (ref "U16") (pin "1") (pinfunction "OC_1") (pintype "input"))
      (node (ref "U8") (pin "15") (pinfunction "Y0_15") (pintype "output"))
    )
    (net (code "103") (name "Net-(U18-7-IN)") (class "Default")
      (node (ref "R91") (pin "1") (pinfunction "1_1") (pintype "passive"))
      (node (ref "U18") (pin "7") (pinfunction "7-IN_7") (pintype "passive"))
    )
    (net (code "104") (name "Net-(U18-11-IN)") (class "Default")
      (node (ref "U18") (pin "11") (pinfunction "11-IN_11") (pintype "passive"))
      (node (ref "U19") (pin "6") (pinfunction "O_6") (pintype "output"))
      (node (ref "U3") (pin "24") (pinfunction "~{OE}_24") (pintype "passive"))
    )
    (net (code "105") (name "Net-(U19A-I0)") (class "Default")
      (node (ref "U19") (pin "1") (pinfunction "I0_1") (pintype "input"))
      (node (ref "U21") (pin "2") (pinfunction "O_2") (pintype "output"))
    )
    (net (code "106") (name "Net-(U19B-I0)") (class "Default")
      (node (ref "U19") (pin "3") (pinfunction "I0_3") (pintype "input"))
      (node (ref "U20") (pin "5") (pinfunction "Y1_5") (pintype "output"))
    )
    (net (code "107") (name "Net-(U19B-I1)") (class "Default")
      (node (ref "U19") (pin "4") (pinfunction "I1_4") (pintype "input"))
      (node (ref "U20") (pin "6") (pinfunction "Y2_6") (pintype "output"))
    )
    (net (code "108") (name "Net-(U19B-I2)") (class "Default")
      (node (ref "U19") (pin "5") (pinfunction "I2_5") (pintype "input"))
      (node (ref "U20") (pin "7") (pinfunction "Y3_7") (pintype "output"))
      (node (ref "U26") (pin "9") (pinfunction "I_9") (pintype "input"))
    )
    (net (code "109") (name "Net-(U19C-I2)") (class "Default")
      (node (ref "U19") (pin "11") (pinfunction "I2_11") (pintype "input"))
      (node (ref "U26") (pin "12") (pinfunction "O_12") (pintype "output"))
    )
    (net (code "110") (name "Net-(U20A-Y0)") (class "Default")
      (node (ref "U20") (pin "15") (pinfunction "G_15") (pintype "input"))
      (node (ref "U20") (pin "4") (pinfunction "Y0_4") (pintype "output"))
    )
    (net (code "111") (name "Net-(U20B-Y1)") (class "Default")
      (node (ref "U20") (pin "11") (pinfunction "Y1_11") (pintype "output"))
      (node (ref "U8") (pin "4") (pinfunction "G2A_4") (pintype "input"))
      (node (ref "U8") (pin "5") (pinfunction "G2B_5") (pintype "input"))
    )
    (net (code "112") (name "Net-(U21C-I)") (class "Default")
      (node (ref "C100") (pin "+") (pinfunction "+_+") (pintype "passive"))
      (node (ref "CR1") (pin "A") (pinfunction "A_A") (pintype "passive"))
      (node (ref "R29") (pin "1") (pinfunction "1_1") (pintype "passive"))
      (node (ref "U21") (pin "9") (pinfunction "I_9") (pintype "input"))
    )
    (net (code "113") (name "Net-(U21C-O)") (class "Default")
      (node (ref "U21") (pin "1") (pinfunction "I_1") (pintype "input"))
      (node (ref "U21") (pin "8") (pinfunction "O_8") (pintype "output"))
    )
    (net (code "114") (name "Net-(U21F-I)") (class "Default")
      (node (ref "U21") (pin "5") (pinfunction "I_5") (pintype "input"))
      (node (ref "Y2") (pin "3") (pinfunction "OUT_3") (pintype "bidirectional"))
    )
    (net (code "115") (name "Net-(U21F-O)") (class "Default")
      (node (ref "U21") (pin "6") (pinfunction "O_6") (pintype "output"))
      (node (ref "U22") (pin "3") (pinfunction "CLK_3") (pintype "input"))
      (node (ref "U23") (pin "3") (pinfunction "CLK_3") (pintype "input"))
    )
    (net (code "116") (name "Net-(U22A-D)") (class "Default")
      (node (ref "U22") (pin "2") (pinfunction "D_2") (pintype "input"))
      (node (ref "U23") (pin "5") (pinfunction "Q_5") (pintype "output"))
      (node (ref "U4") (pin "35") (pinfunction "Q_35") (pintype "passive"))
    )
    (net (code "117") (name "Net-(U22A-PRE)") (class "Default")
      (node (ref "R10") (pin "1") (pinfunction "1_1") (pintype "passive"))
      (node (ref "U22") (pin "10") (pinfunction "PRE_10") (pintype "input"))
      (node (ref "U22") (pin "11") (pinfunction "CLK_11") (pintype "input"))
      (node (ref "U22") (pin "12") (pinfunction "D_12") (pintype "input"))
      (node (ref "U22") (pin "4") (pinfunction "PRE_4") (pintype "input"))
      (node (ref "U23") (pin "4") (pinfunction "PRE_4") (pintype "input"))
      (node (ref "U9") (pin "4") (pinfunction "PRE_4") (pintype "input"))
    )
    (net (code "118") (name "Net-(U22A-Q)") (class "Default")
      (node (ref "U22") (pin "5") (pinfunction "Q_5") (pintype "output"))
      (node (ref "U9") (pin "3") (pinfunction "CLK_3") (pintype "input"))
    )
    (net (code "119") (name "Net-(U23B-CLK)") (class "Default")
      (node (ref "U23") (pin "11") (pinfunction "CLK_11") (pintype "input"))
      (node (ref "U25") (pin "13") (pinfunction "OUTD_13") (pintype "bidirectional"))
    )
    (net (code "120") (name "Net-(U23B-D)") (class "Default")
      (node (ref "R4") (pin "1") (pinfunction "1_1") (pintype "passive"))
      (node (ref "U23") (pin "12") (pinfunction "D_12") (pintype "input"))
      (node (ref "U24") (pin "12") (pinfunction "~{EN}_12") (pintype "bidirectional"))
      (node (ref "U25") (pin "12") (pinfunction "~{EN}_12") (pintype "bidirectional"))
      (node (ref "U5") (pin "1") (pinfunction "OC_1") (pintype "input"))
    )
    (net (code "121") (name "Net-(U24-OUTA)") (class "Default")
      (node (ref "R21") (pin "1") (pinfunction "1_1") (pintype "passive"))
      (node (ref "U24") (pin "2") (pinfunction "OUTA_2") (pintype "bidirectional"))
    )
    (net (code "122") (name "Net-(U24-OUTB)") (class "Default")
      (node (ref "R20") (pin "1") (pinfunction "1_1") (pintype "passive"))
      (node (ref "U24") (pin "6") (pinfunction "OUTB_6") (pintype "bidirectional"))
    )
    (net (code "123") (name "Net-(U24-OUTD)") (class "Default")
      (node (ref "R19") (pin "1") (pinfunction "1_1") (pintype "passive"))
      (node (ref "U24") (pin "14") (pinfunction "OUTD_14") (pintype "bidirectional"))
    )
    (net (code "124") (name "Net-(U26A-I)") (class "Default")
      (node (ref "C49") (pin "1") (pinfunction "1_1") (pintype "passive"))
      (node (ref "R32") (pin "1") (pinfunction "1_1") (pintype "passive"))
      (node (ref "U26") (pin "1") (pinfunction "I_1") (pintype "input"))
      (node (ref "Y1") (pin "1") (pinfunction "1_1") (pintype "passive"))
    )
    (net (code "125") (name "Net-(U26A-O)") (class "Default")
      (node (ref "R32") (pin "2") (pinfunction "2_2") (pintype "passive"))
      (node (ref "R34") (pin "1") (pinfunction "1_1") (pintype "passive"))
      (node (ref "U26") (pin "2") (pinfunction "O_2") (pintype "output"))
      (node (ref "U26") (pin "3") (pinfunction "I_3") (pintype "input"))
    )
    (net (code "126") (name "Net-(U26B-O)") (class "Default")
      (node (ref "C47") (pin "2") (pinfunction "2_2") (pintype "passive"))
      (node (ref "R34") (pin "2") (pinfunction "2_2") (pintype "passive"))
      (node (ref "U26") (pin "4") (pinfunction "O_4") (pintype "output"))
      (node (ref "U26") (pin "5") (pinfunction "I_5") (pintype "input"))
    )
    (net (code "127") (name "Net-(U28-BIAS)") (class "Default")
      (node (ref "C55") (pin "2") (pinfunction "2_2") (pintype "passive"))
      (node (ref "R41") (pin "2") (pinfunction "2_2") (pintype "passive"))
      (node (ref "U28") (pin "13") (pinfunction "BIAS_13") (pintype "passive"))
      (node (ref "U29") (pin "7") (pinfunction "OUT_7") (pintype "output"))
    )
    (net (code "128") (name "Net-(U28-BIAS+)") (class "Default")
      (node (ref "C64") (pin "+") (pinfunction "+_+") (pintype "passive"))
      (node (ref "U28") (pin "15") (pinfunction "BIAS+_15") (pintype "passive"))
      (node (ref "U29") (pin "5") (pinfunction "+IN_5") (pintype "input"))
    )
    (net (code "129") (name "Net-(U28-BIAS-)") (class "Default")
      (node (ref "C55") (pin "1") (pinfunction "1_1") (pintype "passive"))
      (node (ref "U28") (pin "14") (pinfunction "BIAS-_14") (pintype "passive"))
      (node (ref "U29") (pin "6") (pinfunction "-IN_6") (pintype "input"))
    )
    (net (code "130") (name "Net-(U28-BUFF)") (class "Default")
      (node (ref "U28") (pin "12") (pinfunction "BUFF_12") (pintype "passive"))
      (node (ref "U29") (pin "3") (pinfunction "+IN_3") (pintype "input"))
    )
    (net (code "131") (name "Net-(U28-CH1)") (class "Default")
      (node (ref "C51") (pin "1") (pinfunction "1_1") (pintype "passive"))
      (node (ref "C53") (pin "-") (pinfunction "-_-") (pintype "passive"))
      (node (ref "U28") (pin "9") (pinfunction "CH1_9") (pintype "passive"))
    )
    (net (code "132") (name "Net-(U28-CH2)") (class "Default")
      (node (ref "C56") (pin "1") (pinfunction "1_1") (pintype "passive"))
      (node (ref "C57") (pin "-") (pinfunction "-_-") (pintype "passive"))
      (node (ref "U28") (pin "10") (pinfunction "CH2_10") (pintype "passive"))
    )
    (net (code "133") (name "Net-(U28-COM)") (class "Default")
      (node (ref "R43") (pin "2") (pinfunction "2_2") (pintype "passive"))
      (node (ref "U28") (pin "11") (pinfunction "COM_11") (pintype "passive"))
    )
    (net (code "134") (name "Net-(U29A--IN)") (class "Default")
      (node (ref "R43") (pin "1") (pinfunction "1_1") (pintype "passive"))
      (node (ref "U29") (pin "1") (pinfunction "OUT_1") (pintype "output"))
      (node (ref "U29") (pin "2") (pinfunction "-IN_2") (pintype "input"))
    )
    (net (code "135") (name "Net-(U29C-+IN)") (class "Default")
      (node (ref "C67") (pin "+") (pinfunction "+_+") (pintype "passive"))
      (node (ref "R55") (pin "1") (pinfunction "1_1") (pintype "passive"))
      (node (ref "R60") (pin "2") (pinfunction "2_2") (pintype "passive"))
      (node (ref "U29") (pin "10") (pinfunction "+IN_10") (pintype "input"))
    )
    (net (code "136") (name "Net-(U29D--IN)") (class "Default")
      (node (ref "C67") (pin "-") (pinfunction "-_-") (pintype "passive"))
      (node (ref "R59") (pin "2") (pinfunction "2_2") (pintype "passive"))
      (node (ref "U29") (pin "13") (pinfunction "-IN_13") (pintype "input"))
      (node (ref "U29") (pin "14") (pinfunction "OUT_14") (pintype "output"))
    )
    (net (code "137") (name "Net-(U30-CNTL)") (class "Default")
      (node (ref "C66") (pin "+") (pinfunction "+_+") (pintype "passive"))
      (node (ref "C97") (pin "2") (pinfunction "2_2") (pintype "passive"))
      (node (ref "R87") (pin "1") (pinfunction "1_1") (pintype "passive"))
      (node (ref "U30") (pin "2") (pinfunction "CNTL_2") (pintype "passive"))
    )
    (net (code "138") (name "Net-(U30-ROLOFF)") (class "Default")
      (node (ref "C76") (pin "1") (pinfunction "1_1") (pintype "passive"))
      (node (ref "U30") (pin "5") (pinfunction "ROLOFF_5") (pintype "passive"))
    )
    (net (code "139") (name "Net-(U30-VIN)") (class "Default")
      (node (ref "C68") (pin "-") (pinfunction "-_-") (pintype "passive"))
      (node (ref "U30") (pin "1") (pinfunction "VIN_1") (pintype "bidirectional"))
    )
    (net (code "140") (name "Net-(U30-VO)") (class "Default")
      (node (ref "R71") (pin "1") (pinfunction "1_1") (pintype "passive"))
      (node (ref "U30") (pin "7") (pinfunction "VO_7") (pintype "output"))
    )
    (net (code "141") (name "Net-(U31-BS-I)") (class "Default")
      (node (ref "C86") (pin "+") (pinfunction "+_+") (pintype "passive"))
      (node (ref "U31") (pin "9") (pinfunction "BS-I_9") (pintype "passive"))
    )
    (net (code "142") (name "Net-(U31-BS-M)") (class "Default")
      (node (ref "C87") (pin "+") (pinfunction "+_+") (pintype "passive"))
      (node (ref "U31") (pin "12") (pinfunction "BS-M_12") (pintype "output"))
    )
    (net (code "143") (name "Net-(U31-BYPASS)") (class "Default")
      (node (ref "C84") (pin "+") (pinfunction "+_+") (pintype "passive"))
      (node (ref "R92") (pin "2") (pinfunction "2_2") (pintype "passive"))
      (node (ref "U31") (pin "5") (pinfunction "BYPASS_5") (pintype "passive"))
    )
    (net (code "144") (name "Net-(U31-FEEDBACK)") (class "Default")
      (node (ref "C83") (pin "+") (pinfunction "+_+") (pintype "passive"))
      (node (ref "U31") (pin "4") (pinfunction "FEEDBACK_4") (pintype "passive"))
    )
    (net (code "145") (name "Net-(U31-IN)") (class "Default")
      (node (ref "C81") (pin "-") (pinfunction "-_-") (pintype "passive"))
      (node (ref "R92") (pin "1") (pinfunction "1_1") (pintype "passive"))
      (node (ref "U31") (pin "1") (pinfunction "IN_1") (pintype "passive"))
    )
    (net (code "146") (name "Net-(U31-MUTE)") (class "Default")
      (node (ref "C80") (pin "+") (pinfunction "+_+") (pintype "passive"))
      (node (ref "U31") (pin "6") (pinfunction "MUTE_6") (pintype "passive"))
    )
    (net (code "147") (name "Net-(U31-OUT(I))") (class "Default")
      (node (ref "C86") (pin "-") (pinfunction "-_-") (pintype "passive"))
      (node (ref "C90") (pin "2") (pinfunction "2_2") (pintype "passive"))
      (node (ref "C92") (pin "2") (pinfunction "2_2") (pintype "passive"))
      (node (ref "P7") (pin "3") (pinfunction "3_3") (pintype "passive"))
      (node (ref "P7") (pin "4") (pinfunction "4_4") (pintype "passive"))
      (node (ref "U31") (pin "8") (pinfunction "OUT(I)_8") (pintype "output"))
    )
    (net (code "148") (name "Net-(U31-OUT(M))") (class "Default")
      (node (ref "C87") (pin "-") (pinfunction "-_-") (pintype "passive"))
      (node (ref "C91") (pin "2") (pinfunction "2_2") (pintype "passive"))
      (node (ref "C92") (pin "1") (pinfunction "1_1") (pintype "passive"))
      (node (ref "P7") (pin "1") (pinfunction "1_1") (pintype "passive"))
      (node (ref "P7") (pin "2") (pinfunction "2_2") (pintype "passive"))
      (node (ref "U31") (pin "10") (pinfunction "OUT(M)_10") (pintype "passive"))
    )
    (net (code "149") (name "Net-(U32A-+IN)") (class "Default")
      (node (ref "C46") (pin "+") (pinfunction "+_+") (pintype "passive"))
      (node (ref "R33") (pin "2") (pinfunction "2_2") (pintype "passive"))
      (node (ref "R48") (pin "1") (pinfunction "1_1") (pintype "passive"))
      (node (ref "U32") (pin "3") (pinfunction "+IN_3") (pintype "input"))
    )
    (net (code "150") (name "Net-(U32A--IN)") (class "Default")
      (node (ref "R39") (pin "2") (pinfunction "2_2") (pintype "passive"))
      (node (ref "U32") (pin "1") (pinfunction "OUT_1") (pintype "output"))
      (node (ref "U32") (pin "2") (pinfunction "-IN_2") (pintype "input"))
    )
    (net (code "151") (name "Net-(U32B-+IN)") (class "Default")
      (node (ref "C48") (pin "1") (pinfunction "1_1") (pintype "passive"))
      (node (ref "R36") (pin "1") (pinfunction "1_1") (pintype "passive"))
      (node (ref "U32") (pin "5") (pinfunction "+IN_5") (pintype "input"))
    )
    (net (code "152") (name "Net-(U32C--IN)") (class "Default")
      (node (ref "C59") (pin "2") (pinfunction "2_2") (pintype "passive"))
      (node (ref "R46") (pin "1") (pinfunction "1_1") (pintype "passive"))
      (node (ref "U32") (pin "9") (pinfunction "-IN_9") (pintype "input"))
    )
    (net (code "153") (name "Net-(U32C-OUT)") (class "Default")
      (node (ref "C59") (pin "1") (pinfunction "1_1") (pintype "passive"))
      (node (ref "R45") (pin "1") (pinfunction "1_1") (pintype "passive"))
      (node (ref "R78") (pin "2") (pinfunction "2_2") (pintype "passive"))
      (node (ref "U32") (pin "8") (pinfunction "OUT_8") (pintype "output"))
    )
    (net (code "154") (name "Net-(U32D-+IN)") (class "Default")
      (node (ref "C50") (pin "1") (pinfunction "1_1") (pintype "passive"))
      (node (ref "R38") (pin "1") (pinfunction "1_1") (pintype "passive"))
      (node (ref "U32") (pin "12") (pinfunction "+IN_12") (pintype "input"))
    )
    (net (code "155") (name "Net-(U32D--IN)") (class "Default")
      (node (ref "C52") (pin "1") (pinfunction "1_1") (pintype "passive"))
      (node (ref "R35") (pin "2") (pinfunction "2_2") (pintype "passive"))
      (node (ref "U32") (pin "13") (pinfunction "-IN_13") (pintype "input"))
      (node (ref "U32") (pin "14") (pinfunction "OUT_14") (pintype "output"))
    )
    (net (code "156") (name "Net-(U33A--IN)") (class "Default")
      (node (ref "C71") (pin "2") (pinfunction "2_2") (pintype "passive"))
      (node (ref "R64") (pin "1") (pinfunction "1_1") (pintype "passive"))
      (node (ref "U33") (pin "2") (pinfunction "-IN_2") (pintype "input"))
    )
    (net (code "157") (name "Net-(U33A-OUT)") (class "Default")
      (node (ref "C71") (pin "1") (pinfunction "1_1") (pintype "passive"))
      (node (ref "R63") (pin "1") (pinfunction "1_1") (pintype "passive"))
      (node (ref "R79") (pin "2") (pinfunction "2_2") (pintype "passive"))
      (node (ref "U33") (pin "1") (pinfunction "OUT_1") (pintype "output"))
    )
    (net (code "158") (name "Net-(U33B--IN)") (class "Default")
      (node (ref "C60") (pin "2") (pinfunction "2_2") (pintype "passive"))
      (node (ref "R52") (pin "1") (pinfunction "1_1") (pintype "passive"))
      (node (ref "U33") (pin "6") (pinfunction "-IN_6") (pintype "input"))
    )
    (net (code "159") (name "Net-(U33B-OUT)") (class "Default")
      (node (ref "C60") (pin "1") (pinfunction "1_1") (pintype "passive"))
      (node (ref "R51") (pin "1") (pinfunction "1_1") (pintype "passive"))
      (node (ref "R77") (pin "2") (pinfunction "2_2") (pintype "passive"))
      (node (ref "U33") (pin "7") (pinfunction "OUT_7") (pintype "output"))
    )
    (net (code "160") (name "Net-(U33D--IN)") (class "Default")
      (node (ref "C96") (pin "1") (pinfunction "1_1") (pintype "passive"))
      (node (ref "R77") (pin "1") (pinfunction "1_1") (pintype "passive"))
      (node (ref "R78") (pin "1") (pinfunction "1_1") (pintype "passive"))
      (node (ref "R79") (pin "1") (pinfunction "1_1") (pintype "passive"))
      (node (ref "R81") (pin "1") (pinfunction "1_1") (pintype "passive"))
      (node (ref "R88") (pin "2") (pinfunction "2_2") (pintype "passive"))
      (node (ref "U33") (pin "13") (pinfunction "-IN_13") (pintype "input"))
    )
    (net (code "161") (name "Net-(U33D-OUT)") (class "Default")
      (node (ref "C68") (pin "+") (pinfunction "+_+") (pintype "passive"))
      (node (ref "C96") (pin "2") (pinfunction "2_2") (pintype "passive"))
      (node (ref "R88") (pin "1") (pinfunction "1_1") (pintype "passive"))
      (node (ref "U33") (pin "14") (pinfunction "OUT_14") (pintype "output"))
    )
    (net (code "162") (name "PCM-A0") (class "Default")
      (node (ref "U1") (pin "18") (pinfunction "A0_18") (pintype "passive"))
      (node (ref "U12") (pin "12") (pinfunction "A0_12") (pintype "passive"))
      (node (ref "U13") (pin "12") (pinfunction "A0_12") (pintype "passive"))
    )
    (net (code "163") (name "PCM-A1") (class "Default")
      (node (ref "U1") (pin "19") (pinfunction "A1_19") (pintype "passive"))
      (node (ref "U12") (pin "11") (pinfunction "A1_11") (pintype "passive"))
      (node (ref "U13") (pin "11") (pinfunction "A1_11") (pintype "passive"))
    )
    (net (code "164") (name "PCM-A2") (class "Default")
      (node (ref "U1") (pin "20") (pinfunction "A2_20") (pintype "passive"))
      (node (ref "U12") (pin "10") (pinfunction "A2_10") (pintype "passive"))
      (node (ref "U13") (pin "10") (pinfunction "A2_10") (pintype "passive"))
    )
    (net (code "165") (name "PCM-A3") (class "Default")
      (node (ref "U1") (pin "21") (pinfunction "A3_21") (pintype "passive"))
      (node (ref "U12") (pin "9") (pinfunction "A3_9") (pintype "passive"))
      (node (ref "U13") (pin "9") (pinfunction "A3_9") (pintype "passive"))
    )
    (net (code "166") (name "PCM-A4") (class "Default")
      (node (ref "U1") (pin "22") (pinfunction "A4_22") (pintype "passive"))
      (node (ref "U12") (pin "8") (pinfunction "A4_8") (pintype "passive"))
      (node (ref "U13") (pin "8") (pinfunction "A4_8") (pintype "passive"))
    )
    (net (code "167") (name "PCM-A5") (class "Default")
      (node (ref "U1") (pin "23") (pinfunction "A5_23") (pintype "passive"))
      (node (ref "U12") (pin "7") (pinfunction "A5_7") (pintype "passive"))
      (node (ref "U13") (pin "7") (pinfunction "A5_7") (pintype "passive"))
    )
    (net (code "168") (name "PCM-A6") (class "Default")
      (node (ref "U1") (pin "24") (pinfunction "A6_24") (pintype "passive"))
      (node (ref "U12") (pin "6") (pinfunction "A6_6") (pintype "passive"))
      (node (ref "U13") (pin "6") (pinfunction "A6_6") (pintype "passive"))
    )
    (net (code "169") (name "PCM-A7") (class "Default")
      (node (ref "U1") (pin "25") (pinfunction "A7_25") (pintype "passive"))
      (node (ref "U12") (pin "5") (pinfunction "A7_5") (pintype "passive"))
      (node (ref "U13") (pin "5") (pinfunction "A7_5") (pintype "passive"))
    )
    (net (code "170") (name "PCM-A8") (class "Default")
      (node (ref "U1") (pin "26") (pinfunction "A8_26") (pintype "passive"))
      (node (ref "U12") (pin "27") (pinfunction "A8_27") (pintype "passive"))
      (node (ref "U13") (pin "27") (pinfunction "A8_27") (pintype "passive"))
    )
    (net (code "171") (name "PCM-A9") (class "Default")
      (node (ref "U1") (pin "27") (pinfunction "A9_27") (pintype "passive"))
      (node (ref "U12") (pin "26") (pinfunction "A9_26") (pintype "passive"))
      (node (ref "U13") (pin "26") (pinfunction "A9_26") (pintype "passive"))
    )
    (net (code "172") (name "PCM-A10") (class "Default")
      (node (ref "U1") (pin "28") (pinfunction "A10_28") (pintype "passive"))
      (node (ref "U12") (pin "23") (pinfunction "A10_23") (pintype "passive"))
      (node (ref "U13") (pin "23") (pinfunction "A10_23") (pintype "passive"))
    )
    (net (code "173") (name "PCM-A11") (class "Default")
      (node (ref "U1") (pin "29") (pinfunction "A11_29") (pintype "passive"))
      (node (ref "U12") (pin "25") (pinfunction "A11_25") (pintype "passive"))
      (node (ref "U13") (pin "25") (pinfunction "A11_25") (pintype "passive"))
    )
    (net (code "174") (name "PCM-A12") (class "Default")
      (node (ref "U1") (pin "30") (pinfunction "A12_30") (pintype "passive"))
      (node (ref "U12") (pin "4") (pinfunction "A12_4") (pintype "passive"))
      (node (ref "U13") (pin "4") (pinfunction "A12_4") (pintype "passive"))
    )
    (net (code "175") (name "PCM-A13") (class "Default")
      (node (ref "U1") (pin "31") (pinfunction "A13_31") (pintype "passive"))
      (node (ref "U12") (pin "28") (pinfunction "A13_28") (pintype "passive"))
      (node (ref "U13") (pin "28") (pinfunction "A13_28") (pintype "passive"))
    )
    (net (code "176") (name "PCM-A14") (class "Default")
      (node (ref "U1") (pin "32") (pinfunction "A14_32") (pintype "passive"))
      (node (ref "U12") (pin "29") (pinfunction "A14_29") (pintype "passive"))
      (node (ref "U13") (pin "29") (pinfunction "A14_29") (pintype "passive"))
    )
    (net (code "177") (name "PCM-A15") (class "Default")
      (node (ref "U1") (pin "33") (pinfunction "A15_33") (pintype "passive"))
      (node (ref "U12") (pin "3") (pinfunction "A15_3") (pintype "passive"))
      (node (ref "U13") (pin "3") (pinfunction "A15_3") (pintype "passive"))
    )
    (net (code "178") (name "PCM-A16") (class "Default")
      (node (ref "U1") (pin "34") (pinfunction "A16_34") (pintype "passive"))
      (node (ref "U12") (pin "2") (pinfunction "A16_2") (pintype "passive"))
      (node (ref "U13") (pin "2") (pinfunction "A16_2") (pintype "passive"))
    )
    (net (code "179") (name "PCM-A17") (class "Default")
      (node (ref "U1") (pin "35") (pinfunction "A17_35") (pintype "passive"))
      (node (ref "U18") (pin "4") (pinfunction "4-IN_4") (pintype "passive"))
      (node (ref "U26") (pin "13") (pinfunction "I_13") (pintype "input"))
    )
    (net (code "180") (name "PCM-BS") (class "Default")
      (node (ref "U17") (pin "9") (pinfunction "CLK_9") (pintype "input"))
      (node (ref "U8") (pin "10") (pinfunction "Y5_10") (pintype "output"))
    )
    (net (code "181") (name "PCM-D0") (class "Default")
      (node (ref "U1") (pin "9") (pinfunction "SD0_9") (pintype "passive"))
      (node (ref "U12") (pin "13") (pinfunction "D0_13") (pintype "passive"))
      (node (ref "U13") (pin "13") (pinfunction "D0_13") (pintype "passive"))
    )
    (net (code "182") (name "PCM-D1") (class "Default")
      (node (ref "U1") (pin "10") (pinfunction "SD1_10") (pintype "passive"))
      (node (ref "U12") (pin "14") (pinfunction "D1_14") (pintype "passive"))
      (node (ref "U13") (pin "14") (pinfunction "D1_14") (pintype "passive"))
    )
    (net (code "183") (name "PCM-D2") (class "Default")
      (node (ref "U1") (pin "11") (pinfunction "SD2_11") (pintype "passive"))
      (node (ref "U12") (pin "15") (pinfunction "D2_15") (pintype "passive"))
      (node (ref "U13") (pin "15") (pinfunction "D2_15") (pintype "passive"))
    )
    (net (code "184") (name "PCM-D3") (class "Default")
      (node (ref "U1") (pin "12") (pinfunction "SD3_12") (pintype "passive"))
      (node (ref "U12") (pin "17") (pinfunction "D3_17") (pintype "passive"))
      (node (ref "U13") (pin "17") (pinfunction "D3_17") (pintype "passive"))
      (node (ref "U13") (pin "18") (pinfunction "D4_18") (pintype "passive"))
    )
    (net (code "185") (name "PCM-D4") (class "Default")
      (node (ref "U1") (pin "13") (pinfunction "SD4_13") (pintype "passive"))
      (node (ref "U12") (pin "18") (pinfunction "D4_18") (pintype "passive"))
    )
    (net (code "186") (name "PCM-D5") (class "Default")
      (node (ref "U1") (pin "14") (pinfunction "SD5_14") (pintype "passive"))
      (node (ref "U12") (pin "19") (pinfunction "D5_19") (pintype "passive"))
      (node (ref "U13") (pin "19") (pinfunction "D5_19") (pintype "passive"))
    )
    (net (code "187") (name "PCM-D6") (class "Default")
      (node (ref "U1") (pin "15") (pinfunction "SD6_15") (pintype "passive"))
      (node (ref "U12") (pin "20") (pinfunction "D6_20") (pintype "passive"))
      (node (ref "U13") (pin "20") (pinfunction "D6_20") (pintype "passive"))
    )
    (net (code "188") (name "PCM-D7") (class "Default")
      (node (ref "U1") (pin "16") (pinfunction "SD7_16") (pintype "passive"))
      (node (ref "U12") (pin "21") (pinfunction "D7_21") (pintype "passive"))
      (node (ref "U13") (pin "21") (pinfunction "D7_21") (pintype "passive"))
    )
    (net (code "189") (name "PCM-OUT") (class "Default")
      (node (ref "C58") (pin "1") (pinfunction "1_1") (pintype "passive"))
      (node (ref "R81") (pin "2") (pinfunction "2_2") (pintype "passive"))
      (node (ref "U32") (pin "6") (pinfunction "-IN_6") (pintype "input"))
      (node (ref "U32") (pin "7") (pinfunction "OUT_7") (pintype "output"))
    )
    (net (code "190") (name "RA17-0") (class "Default")
      (node (ref "U12") (pin "30") (pinfunction "A17_30") (pintype "passive"))
      (node (ref "U18") (pin "17") (pinfunction "I/O-17_17") (pintype "passive"))
    )
    (net (code "191") (name "RA17-1") (class "Default")
      (node (ref "U13") (pin "30") (pinfunction "A17_30") (pintype "passive"))
      (node (ref "U18") (pin "14") (pinfunction "I/O-14_14") (pintype "passive"))
    )
    (net (code "192") (name "RA18-0") (class "Default")
      (node (ref "U12") (pin "31") (pinfunction "A18_31") (pintype "passive"))
      (node (ref "U18") (pin "12") (pinfunction "OUT-12_12") (pintype "passive"))
    )
    (net (code "193") (name "RA18-1") (class "Default")
      (node (ref "U13") (pin "31") (pinfunction "A18_31") (pintype "passive"))
      (node (ref "U18") (pin "13") (pinfunction "I/O-13_13") (pintype "passive"))
    )
    (net (code "194") (name "RD-LATCH") (class "Default")
      (node (ref "U10") (pin "12") (pinfunction "~{EN}_12") (pintype "bidirectional"))
      (node (ref "U23") (pin "10") (pinfunction "PRE_10") (pintype "input"))
      (node (ref "U24") (pin "7") (pinfunction "INB_7") (pintype "input"))
      (node (ref "U6") (pin "12") (pinfunction "~{EN}_12") (pintype "bidirectional"))
      (node (ref "U8") (pin "11") (pinfunction "Y4_11") (pintype "output"))
    )
    (net (code "195") (name "RESET") (class "Default")
      (node (ref "R3") (pin "1") (pinfunction "1_1") (pintype "passive"))
      (node (ref "U1") (pin "8") (pinfunction "~{RESET}_8") (pintype "passive"))
      (node (ref "U14") (pin "3") (pinfunction "~{RESET}_3") (pintype "passive"))
      (node (ref "U19") (pin "12") (pinfunction "O_12") (pintype "output"))
      (node (ref "U28") (pin "7") (pinfunction "~{RESET}_7") (pintype "passive"))
      (node (ref "U4") (pin "37") (pinfunction "~{RESET}_37") (pintype "passive"))
    )
    (net (code "196") (name "R{slash}W") (class "Default")
      (node (ref "U18") (pin "9") (pinfunction "9-IN_9") (pintype "passive"))
      (node (ref "U4") (pin "32") (pinfunction "R/W_32") (pintype "passive"))
    )
    (net (code "197") (name "SNDVIDRD") (class "Default")
      (node (ref "C105") (pin "2") (pinfunction "2_2") (pintype "passive"))
      (node (ref "R86") (pin "1") (pinfunction "1_1") (pintype "passive"))
      (node (ref "R95") (pin "1") (pinfunction "1_1") (pintype "passive"))
      (node (ref "U25") (pin "10") (pinfunction "INC_10") (pintype "bidirectional"))
    )
    (net (code "198") (name "SND_DAT0") (class "Default")
      (node (ref "C35") (pin "1") (pinfunction "1_1") (pintype "passive"))
      (node (ref "P1") (pin "3") (pinfunction "3_3") (pintype "passive"))
      (node (ref "R11") (pin "2") (pinfunction "2_2") (pintype "passive"))
    )
    (net (code "199") (name "SND_DAT1") (class "Default")
      (node (ref "C37") (pin "1") (pinfunction "1_1") (pintype "passive"))
      (node (ref "P1") (pin "4") (pinfunction "4_4") (pintype "passive"))
      (node (ref "R13") (pin "2") (pinfunction "2_2") (pintype "passive"))
    )
    (net (code "200") (name "SND_DAT2") (class "Default")
      (node (ref "C38") (pin "1") (pinfunction "1_1") (pintype "passive"))
      (node (ref "P1") (pin "5") (pinfunction "5_5") (pintype "passive"))
      (node (ref "R14") (pin "2") (pinfunction "2_2") (pintype "passive"))
    )
    (net (code "201") (name "SND_DAT3") (class "Default")
      (node (ref "C36") (pin "1") (pinfunction "1_1") (pintype "passive"))
      (node (ref "P1") (pin "6") (pinfunction "6_6") (pintype "passive"))
      (node (ref "R12") (pin "2") (pinfunction "2_2") (pintype "passive"))
    )
    (net (code "202") (name "SND_DAT4") (class "Default")
      (node (ref "C39") (pin "1") (pinfunction "1_1") (pintype "passive"))
      (node (ref "P1") (pin "7") (pinfunction "7_7") (pintype "passive"))
      (node (ref "R15") (pin "2") (pinfunction "2_2") (pintype "passive"))
    )
    (net (code "203") (name "SND_DAT5") (class "Default")
      (node (ref "C40") (pin "1") (pinfunction "1_1") (pintype "passive"))
      (node (ref "P1") (pin "8") (pinfunction "8_8") (pintype "passive"))
      (node (ref "R16") (pin "2") (pinfunction "2_2") (pintype "passive"))
    )
    (net (code "204") (name "SND_DAT6") (class "Default")
      (node (ref "C41") (pin "1") (pinfunction "1_1") (pintype "passive"))
      (node (ref "P1") (pin "9") (pinfunction "9_9") (pintype "passive"))
      (node (ref "R17") (pin "2") (pinfunction "2_2") (pintype "passive"))
    )
    (net (code "205") (name "SND_DAT7") (class "Default")
      (node (ref "C42") (pin "1") (pinfunction "1_1") (pintype "passive"))
      (node (ref "P1") (pin "10") (pinfunction "10_10") (pintype "passive"))
      (node (ref "R18") (pin "2") (pinfunction "2_2") (pintype "passive"))
    )
    (net (code "206") (name "SND_DAT8") (class "Default")
      (node (ref "C107") (pin "1") (pinfunction "1_1") (pintype "passive"))
      (node (ref "R84") (pin "1") (pinfunction "1_1") (pintype "passive"))
      (node (ref "R94") (pin "1") (pinfunction "1_1") (pintype "passive"))
      (node (ref "U25") (pin "2") (pinfunction "INA_2") (pintype "bidirectional"))
    )
    (net (code "207") (name "SND_DAV") (class "Default")
      (node (ref "C45") (pin "1") (pinfunction "1_1") (pintype "passive"))
      (node (ref "P1") (pin "19") (pinfunction "19_19") (pintype "passive"))
      (node (ref "R21") (pin "2") (pinfunction "2_2") (pintype "passive"))
    )
    (net (code "208") (name "SND_RDY") (class "Default")
      (node (ref "C43") (pin "1") (pinfunction "1_1") (pintype "passive"))
      (node (ref "P1") (pin "11") (pinfunction "11_11") (pintype "passive"))
      (node (ref "R19") (pin "2") (pinfunction "2_2") (pintype "passive"))
    )
    (net (code "209") (name "SOFT_RES") (class "Default")
      (node (ref "U19") (pin "13") (pinfunction "I2_13") (pintype "input"))
      (node (ref "U25") (pin "3") (pinfunction "OUTA_3") (pintype "bidirectional"))
    )
    (net (code "210") (name "VIDPWRON") (class "Default")
      (node (ref "U19") (pin "2") (pinfunction "I1_2") (pintype "input"))
      (node (ref "U25") (pin "5") (pinfunction "OUTB_5") (pintype "bidirectional"))
    )
    (net (code "211") (name "VIDSNDRD") (class "Default")
      (node (ref "U11") (pin "12") (pinfunction "~{EN}_12") (pintype "bidirectional"))
      (node (ref "U25") (pin "11") (pinfunction "OUTC_11") (pintype "bidirectional"))
      (node (ref "U7") (pin "12") (pinfunction "~{EN}_12") (pintype "bidirectional"))
      (node (ref "U9") (pin "13") (pinfunction "CLR_13") (pintype "input"))
    )
    (net (code "212") (name "WR-LATCH") (class "Default")
      (node (ref "U5") (pin "11") (pinfunction "CLK_11") (pintype "input"))
      (node (ref "U8") (pin "7") (pinfunction "Y7_7") (pintype "output"))
      (node (ref "U9") (pin "11") (pinfunction "CLK_11") (pintype "input"))
    )
    (net (code "213") (name "YAM") (class "Default")
      (node (ref "U14") (pin "7") (pinfunction "~{CS}_7") (pintype "passive"))
      (node (ref "U8") (pin "14") (pinfunction "Y1_14") (pintype "output"))
    )
    (net (code "214") (name "YAM1-OUT") (class "Default")
      (node (ref "C53") (pin "+") (pinfunction "+_+") (pintype "passive"))
      (node (ref "R40") (pin "2") (pinfunction "2_2") (pintype "passive"))
    )
    (net (code "215") (name "YAM2-OUT") (class "Default")
      (node (ref "C57") (pin "+") (pinfunction "+_+") (pintype "passive"))
      (node (ref "R44") (pin "2") (pinfunction "2_2") (pintype "passive"))
    )
    (net (code "216") (name "unconnected-(P1-Pad2)") (class "Default")
      (node (ref "P1") (pin "2") (pinfunction "2_2") (pintype "passive"))
    )
    (net (code "217") (name "unconnected-(P1-Pad12)") (class "Default")
      (node (ref "P1") (pin "12") (pinfunction "12_12") (pintype "passive"))
    )
    (net (code "218") (name "unconnected-(P1-Pad14)") (class "Default")
      (node (ref "P1") (pin "14") (pinfunction "14_14") (pintype "passive"))
    )
    (net (code "219") (name "unconnected-(P1-Pad20)") (class "Default")
      (node (ref "P1") (pin "20") (pinfunction "20_20") (pintype "passive"))
    )
    (net (code "220") (name "unconnected-(P6-Pad3)") (class "Default")
      (node (ref "P6") (pin "3") (pinfunction "3_3") (pintype "passive"))
    )
    (net (code "221") (name "unconnected-(P6-Pad4)") (class "Default")
      (node (ref "P6") (pin "4") (pinfunction "4_4") (pintype "passive"))
    )
    (net (code "222") (name "unconnected-(U1-~{XTAL}-Pad6)") (class "Default")
      (node (ref "U1") (pin "6") (pinfunction "~{XTAL}_6") (pintype "passive"))
    )
    (net (code "223") (name "unconnected-(U4-AVMA-Pad36)") (class "Default")
      (node (ref "U4") (pin "36") (pinfunction "AVMA_36") (pintype "passive"))
    )
    (net (code "224") (name "unconnected-(U4-BA-Pad6)") (class "Default")
      (node (ref "U4") (pin "6") (pinfunction "BA_6") (pintype "passive"))
    )
    (net (code "225") (name "unconnected-(U4-BS-Pad5)") (class "Default")
      (node (ref "U4") (pin "5") (pinfunction "BS_5") (pintype "passive"))
    )
    (net (code "226") (name "unconnected-(U4-BUSY-Pad33)") (class "Default")
      (node (ref "U4") (pin "33") (pinfunction "BUSY_33") (pintype "passive"))
    )
    (net (code "227") (name "unconnected-(U4-LIC-Pad38)") (class "Default")
      (node (ref "U4") (pin "38") (pinfunction "LIC_38") (pintype "passive"))
    )
    (net (code "228") (name "unconnected-(U4-VCC-Pad7)") (class "Default")
      (node (ref "U4") (pin "7") (pinfunction "VCC_7") (pintype "passive"))
    )
    (net (code "229") (name "unconnected-(U7-~{OUTA}-Pad3)") (class "Default")
      (node (ref "U7") (pin "3") (pinfunction "~{OUTA}_3") (pintype "bidirectional"))
    )
    (net (code "230") (name "unconnected-(U7-~{OUTB}-Pad5)") (class "Default")
      (node (ref "U7") (pin "5") (pinfunction "~{OUTB}_5") (pintype "bidirectional"))
    )
    (net (code "231") (name "unconnected-(U7-~{OUTC}-Pad11)") (class "Default")
      (node (ref "U7") (pin "11") (pinfunction "~{OUTC}_11") (pintype "bidirectional"))
    )
    (net (code "232") (name "unconnected-(U7-~{OUTD}-Pad13)") (class "Default")
      (node (ref "U7") (pin "13") (pinfunction "~{OUTD}_13") (pintype "bidirectional"))
    )
    (net (code "233") (name "unconnected-(U8A-Y6-Pad9)") (class "Default")
      (node (ref "U8") (pin "9") (pinfunction "Y6_9") (pintype "output"))
    )
    (net (code "234") (name "unconnected-(U9B-~{Q}-Pad8)") (class "Default")
      (node (ref "U9") (pin "8") (pinfunction "~{Q}_8") (pintype "output"))
    )
    (net (code "235") (name "unconnected-(U11-~{OUTA}-Pad3)") (class "Default")
      (node (ref "U11") (pin "3") (pinfunction "~{OUTA}_3") (pintype "bidirectional"))
    )
    (net (code "236") (name "unconnected-(U11-~{OUTB}-Pad5)") (class "Default")
      (node (ref "U11") (pin "5") (pinfunction "~{OUTB}_5") (pintype "bidirectional"))
    )
    (net (code "237") (name "unconnected-(U11-~{OUTC}-Pad11)") (class "Default")
      (node (ref "U11") (pin "11") (pinfunction "~{OUTC}_11") (pintype "bidirectional"))
    )
    (net (code "238") (name "unconnected-(U11-~{OUTD}-Pad13)") (class "Default")
      (node (ref "U11") (pin "13") (pinfunction "~{OUTD}_13") (pintype "bidirectional"))
    )
    (net (code "239") (name "unconnected-(U14-CT1-Pad8)") (class "Default")
      (node (ref "U14") (pin "8") (pinfunction "CT1_8") (pintype "passive"))
    )
    (net (code "240") (name "unconnected-(U14-CT2-Pad9)") (class "Default")
      (node (ref "U14") (pin "9") (pinfunction "CT2_9") (pintype "passive"))
    )
    (net (code "241") (name "unconnected-(U15-RFB-Pad16)") (class "Default")
      (node (ref "U15") (pin "16") (pinfunction "RFB_16") (pintype "passive"))
    )
    (net (code "242") (name "unconnected-(U16A-5Q-Pad12)") (class "Default")
      (node (ref "U16") (pin "12") (pinfunction "5Q_12") (pintype "tri_state"))
    )
    (net (code "243") (name "unconnected-(U16A-6Q-Pad15)") (class "Default")
      (node (ref "U16") (pin "15") (pinfunction "6Q_15") (pintype "tri_state"))
    )
    (net (code "244") (name "unconnected-(U16A-7Q-Pad16)") (class "Default")
      (node (ref "U16") (pin "16") (pinfunction "7Q_16") (pintype "tri_state"))
    )
    (net (code "245") (name "unconnected-(U16A-8Q-Pad19)") (class "Default")
      (node (ref "U16") (pin "19") (pinfunction "8Q_19") (pintype "tri_state"))
    )
    (net (code "246") (name "unconnected-(U17A-Q1-Pad2)") (class "Default")
      (node (ref "U17") (pin "2") (pinfunction "Q1_2") (pintype "output"))
    )
    (net (code "247") (name "unconnected-(U17A-Q4-Pad10)") (class "Default")
      (node (ref "U17") (pin "10") (pinfunction "Q4_10") (pintype "output"))
    )
    (net (code "248") (name "unconnected-(U17A-Q5-Pad12)") (class "Default")
      (node (ref "U17") (pin "12") (pinfunction "Q5_12") (pintype "output"))
    )
    (net (code "249") (name "unconnected-(U18-I{slash}O-16-Pad16)") (class "Default")
      (node (ref "U18") (pin "16") (pinfunction "I/O-16_16") (pintype "passive"))
    )
    (net (code "250") (name "unconnected-(U20B-Y2-Pad10)") (class "Default")
      (node (ref "U20") (pin "10") (pinfunction "Y2_10") (pintype "output"))
    )
    (net (code "251") (name "unconnected-(U20B-Y3-Pad9)") (class "Default")
      (node (ref "U20") (pin "9") (pinfunction "Y3_9") (pintype "output"))
    )
    (net (code "252") (name "unconnected-(U22B-Q-Pad9)") (class "Default")
      (node (ref "U22") (pin "9") (pinfunction "Q_9") (pintype "output"))
    )
    (net (code "253") (name "unconnected-(U22B-~{Q}-Pad8)") (class "Default")
      (node (ref "U22") (pin "8") (pinfunction "~{Q}_8") (pintype "output"))
    )
    (net (code "254") (name "unconnected-(U23B-~{Q}-Pad8)") (class "Default")
      (node (ref "U23") (pin "8") (pinfunction "~{Q}_8") (pintype "output"))
    )
    (net (code "255") (name "unconnected-(U24-OUTC-Pad10)") (class "Default")
      (node (ref "U24") (pin "10") (pinfunction "OUTC_10") (pintype "bidirectional"))
    )
    (net (code "256") (name "unconnected-(U24-~{OUTA}-Pad3)") (class "Default")
      (node (ref "U24") (pin "3") (pinfunction "~{OUTA}_3") (pintype "bidirectional"))
    )
    (net (code "257") (name "unconnected-(U24-~{OUTB}-Pad5)") (class "Default")
      (node (ref "U24") (pin "5") (pinfunction "~{OUTB}_5") (pintype "bidirectional"))
    )
    (net (code "258") (name "unconnected-(U24-~{OUTC}-Pad11)") (class "Default")
      (node (ref "U24") (pin "11") (pinfunction "~{OUTC}_11") (pintype "bidirectional"))
    )
    (net (code "259") (name "unconnected-(U24-~{OUTD}-Pad13)") (class "Default")
      (node (ref "U24") (pin "13") (pinfunction "~{OUTD}_13") (pintype "bidirectional"))
    )
    (net (code "260") (name "unconnected-(U31-NC-Pad2)") (class "Default")
      (node (ref "U31") (pin "2") (pinfunction "NC_2") (pintype "no_connect"))
    )
    (net (code "261") (name "unconnected-(Y2-EN-Pad1)") (class "Default")
      (node (ref "Y2") (pin "1") (pinfunction "EN_1") (pintype "bidirectional"))
    )
    (net (code "262") (name "{slash}E") (class "Default")
      (node (ref "C62") (pin "1") (pinfunction "1_1") (pintype "passive"))
      (node (ref "R28") (pin "1") (pinfunction "1_1") (pintype "passive"))
      (node (ref "U18") (pin "5") (pinfunction "5-IN_5") (pintype "passive"))
      (node (ref "U22") (pin "6") (pinfunction "~{Q}_6") (pintype "output"))
      (node (ref "U23") (pin "2") (pinfunction "D_2") (pintype "input"))
    )
    (net (code "263") (name "{slash}EORQ") (class "Default")
      (node (ref "U18") (pin "15") (pinfunction "I/O-15_15") (pintype "passive"))
      (node (ref "U20") (pin "1") (pinfunction "G_1") (pintype "input"))
    )
    (net (code "264") (name "{slash}Q") (class "Default")
      (node (ref "U18") (pin "6") (pinfunction "6-IN_6") (pintype "passive"))
      (node (ref "U23") (pin "6") (pinfunction "~{Q}_6") (pintype "output"))
    )
    (net (code "265") (name "{slash}RD") (class "Default")
      (node (ref "U1") (pin "2") (pinfunction "~{RD}_2") (pintype "passive"))
      (node (ref "U14") (pin "6") (pinfunction "~{RD}_6") (pintype "passive"))
      (node (ref "U18") (pin "18") (pinfunction "I/O-18_18") (pintype "passive"))
      (node (ref "U2") (pin "22") (pinfunction "~{OE}_22") (pintype "input"))
    )
    (net (code "266") (name "{slash}WR") (class "Default")
      (node (ref "U1") (pin "3") (pinfunction "~{WR}_3") (pintype "passive"))
      (node (ref "U14") (pin "5") (pinfunction "~{WR}_5") (pintype "passive"))
      (node (ref "U15") (pin "13") (pinfunction "~{WR}_13") (pintype "input"))
      (node (ref "U18") (pin "19") (pinfunction "OUT-19_19") (pintype "passive"))
      (node (ref "U2") (pin "27") (pinfunction "~{WE}_27") (pintype "input"))
    )
  )
)
